# Master-Slave.net
KiCad netlist of a schematic drawn in Altium Designer
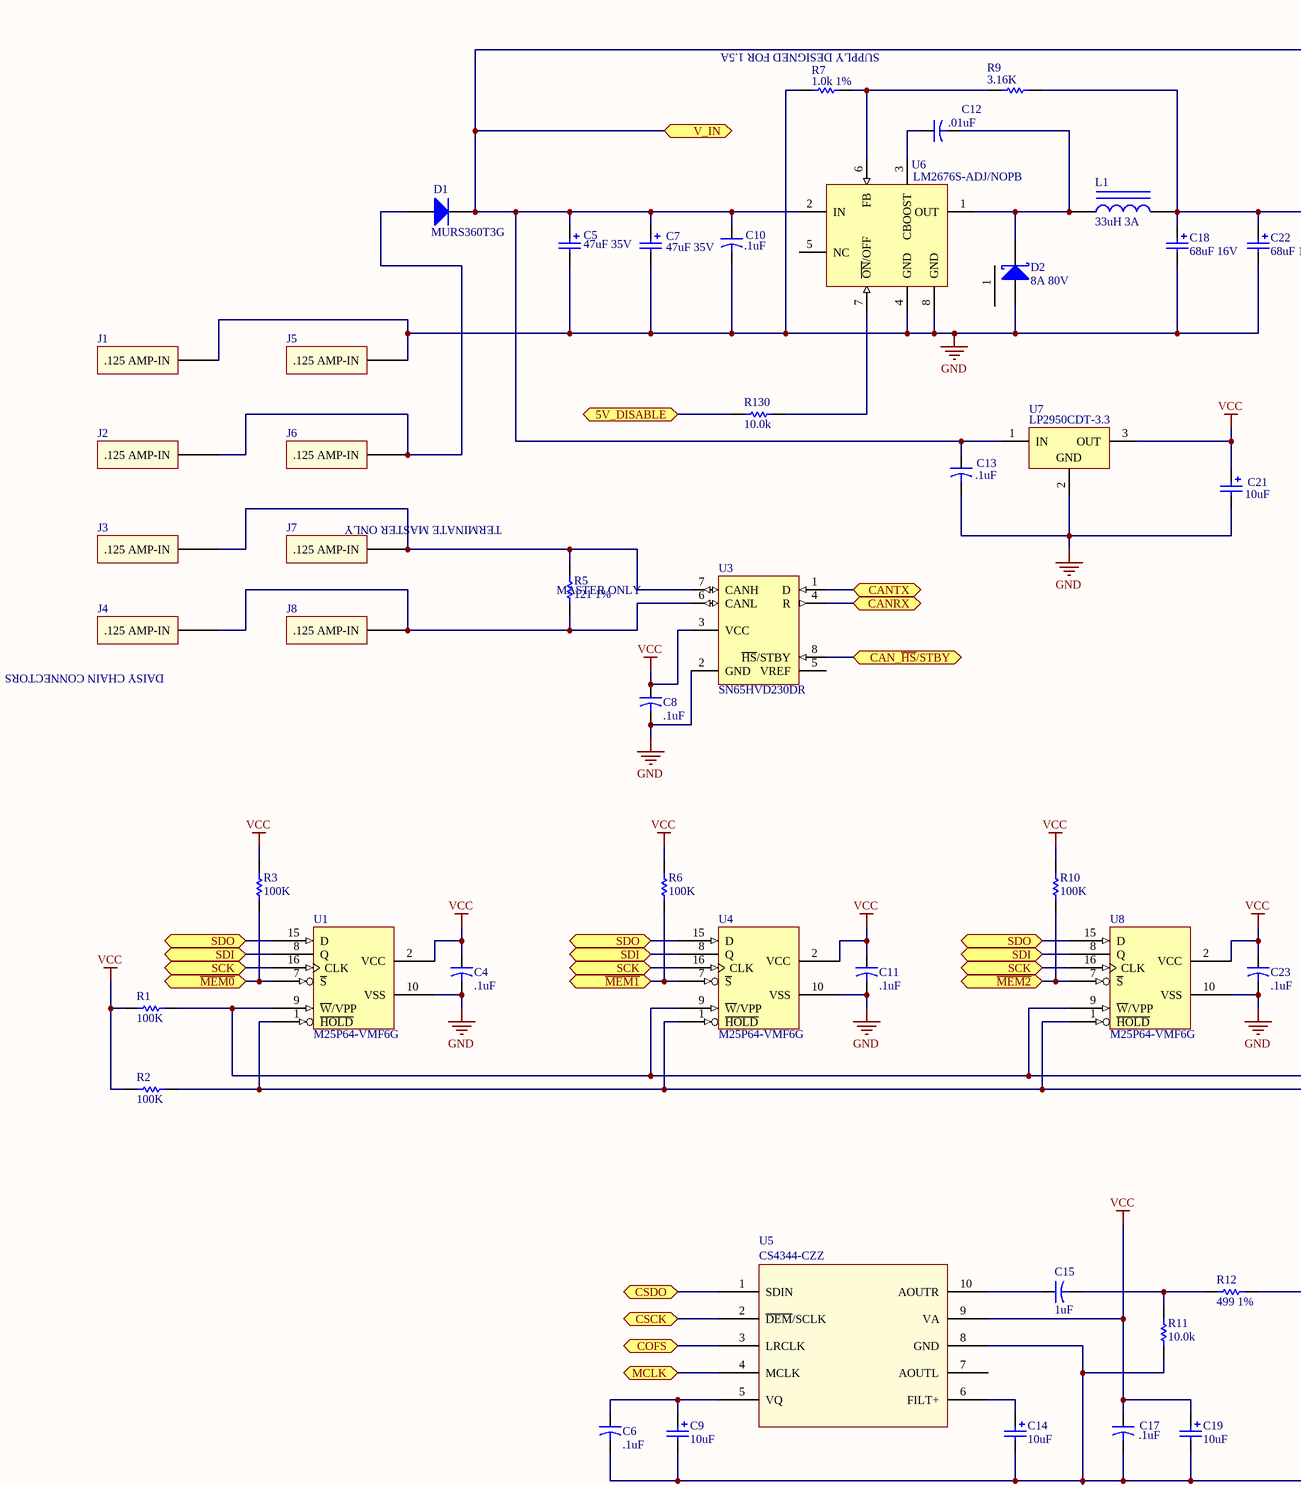
[diagram p0: Master-Slave.SchDoc, top left]
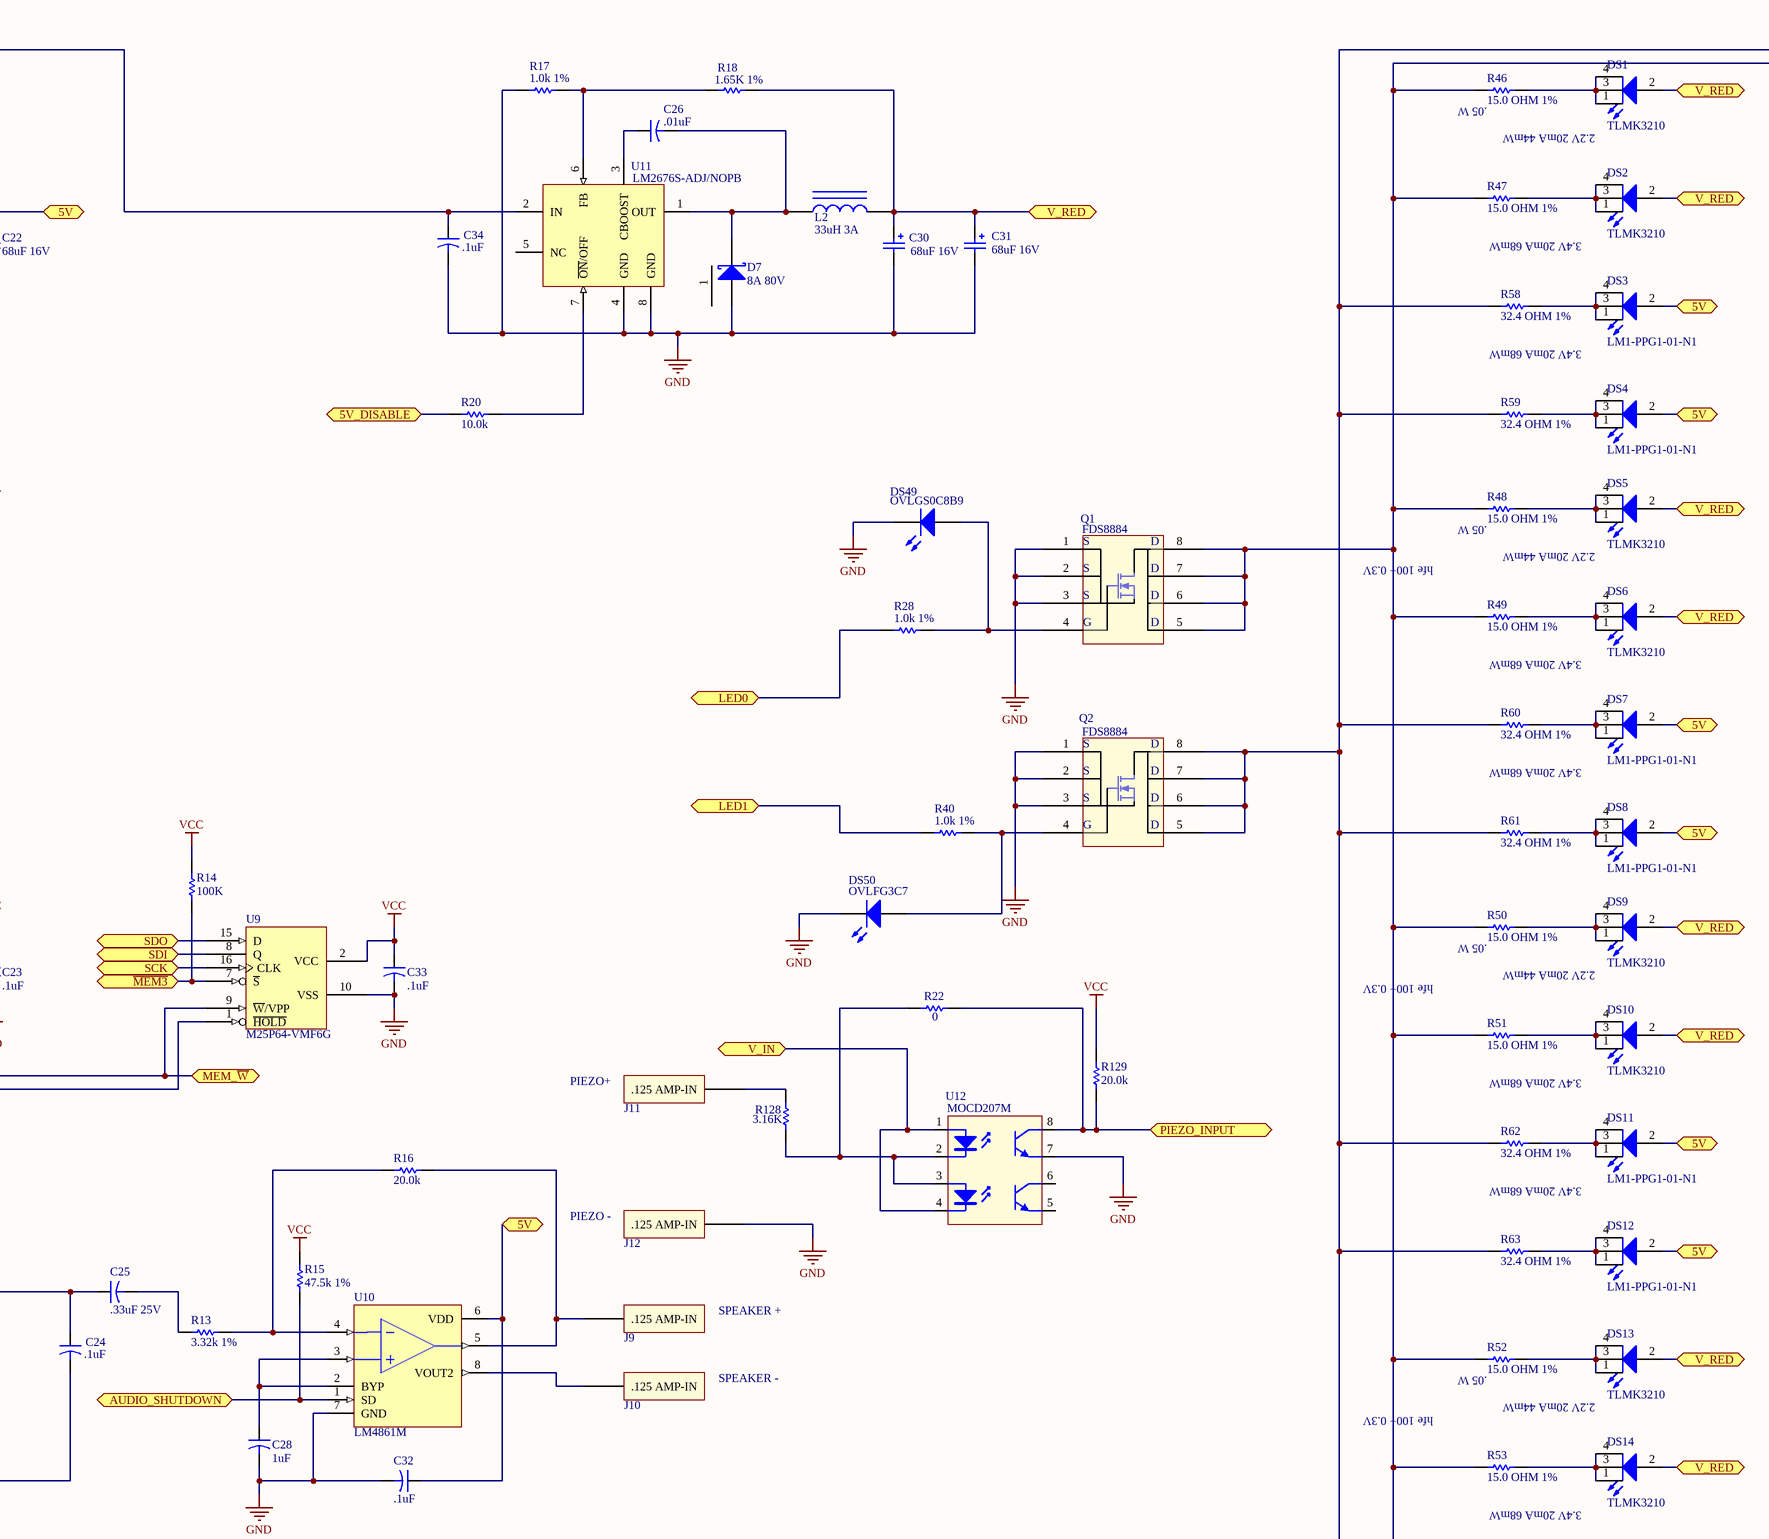
[diagram p1: Master-Slave.SchDoc, top middle]
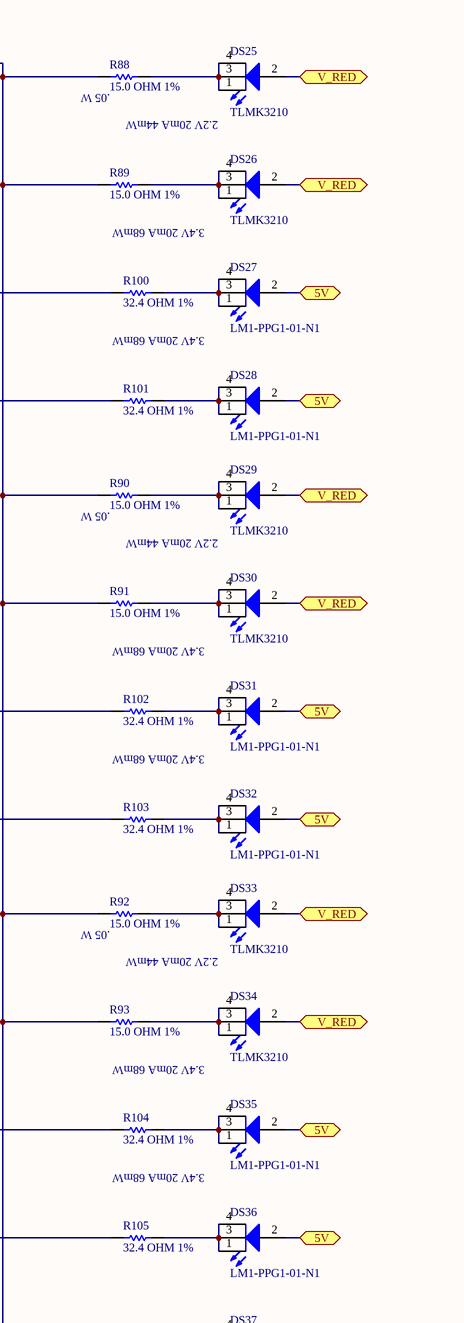
[diagram p2: Master-Slave.SchDoc, top right]
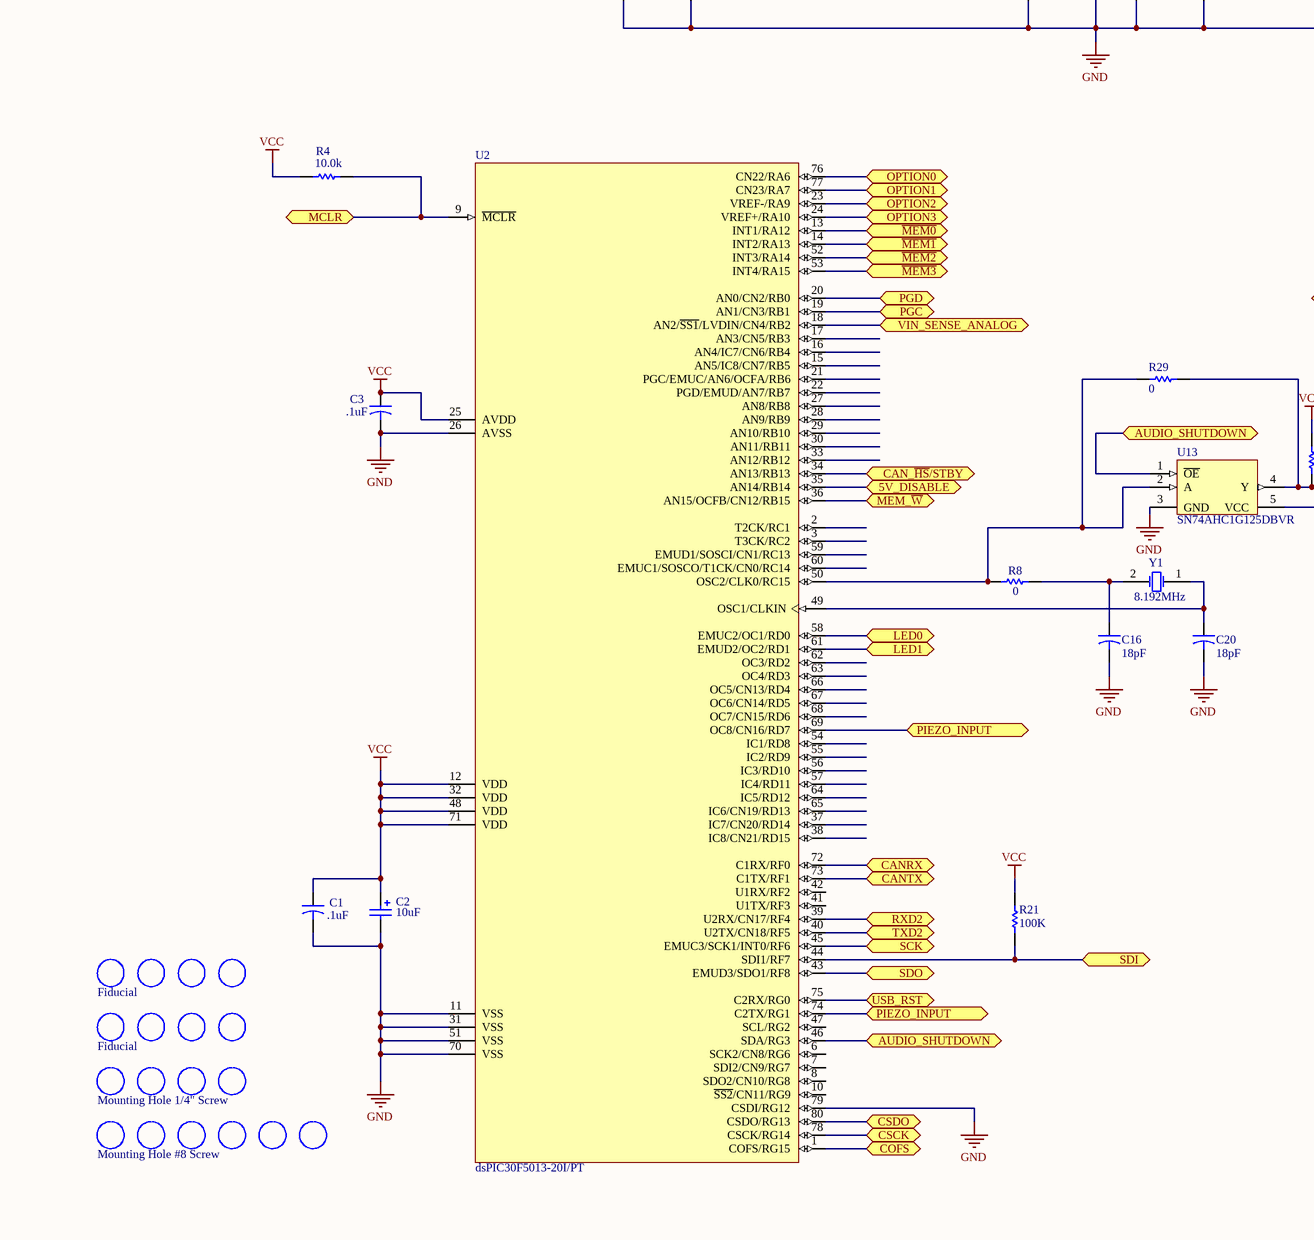
[diagram p3: Master-Slave.SchDoc, bottom left]
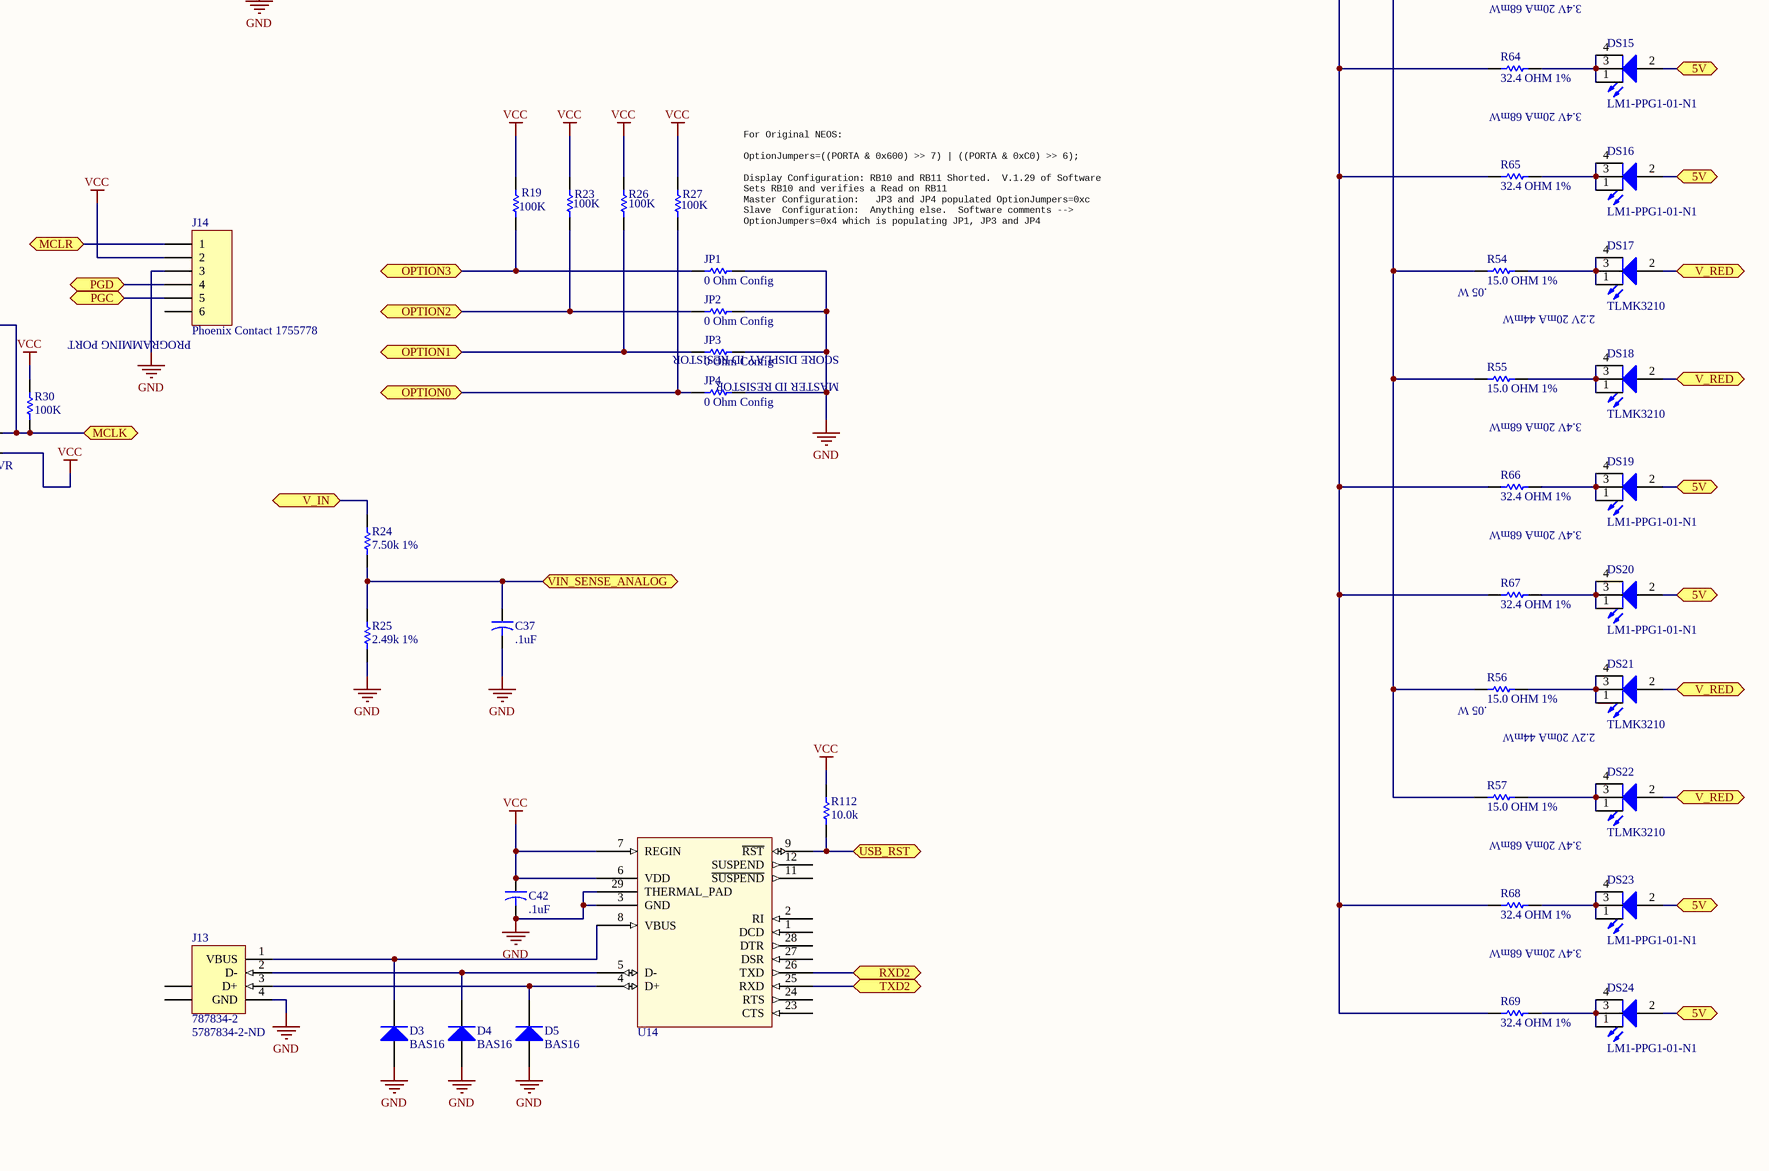
[diagram p4: Master-Slave.SchDoc, bottom middle]
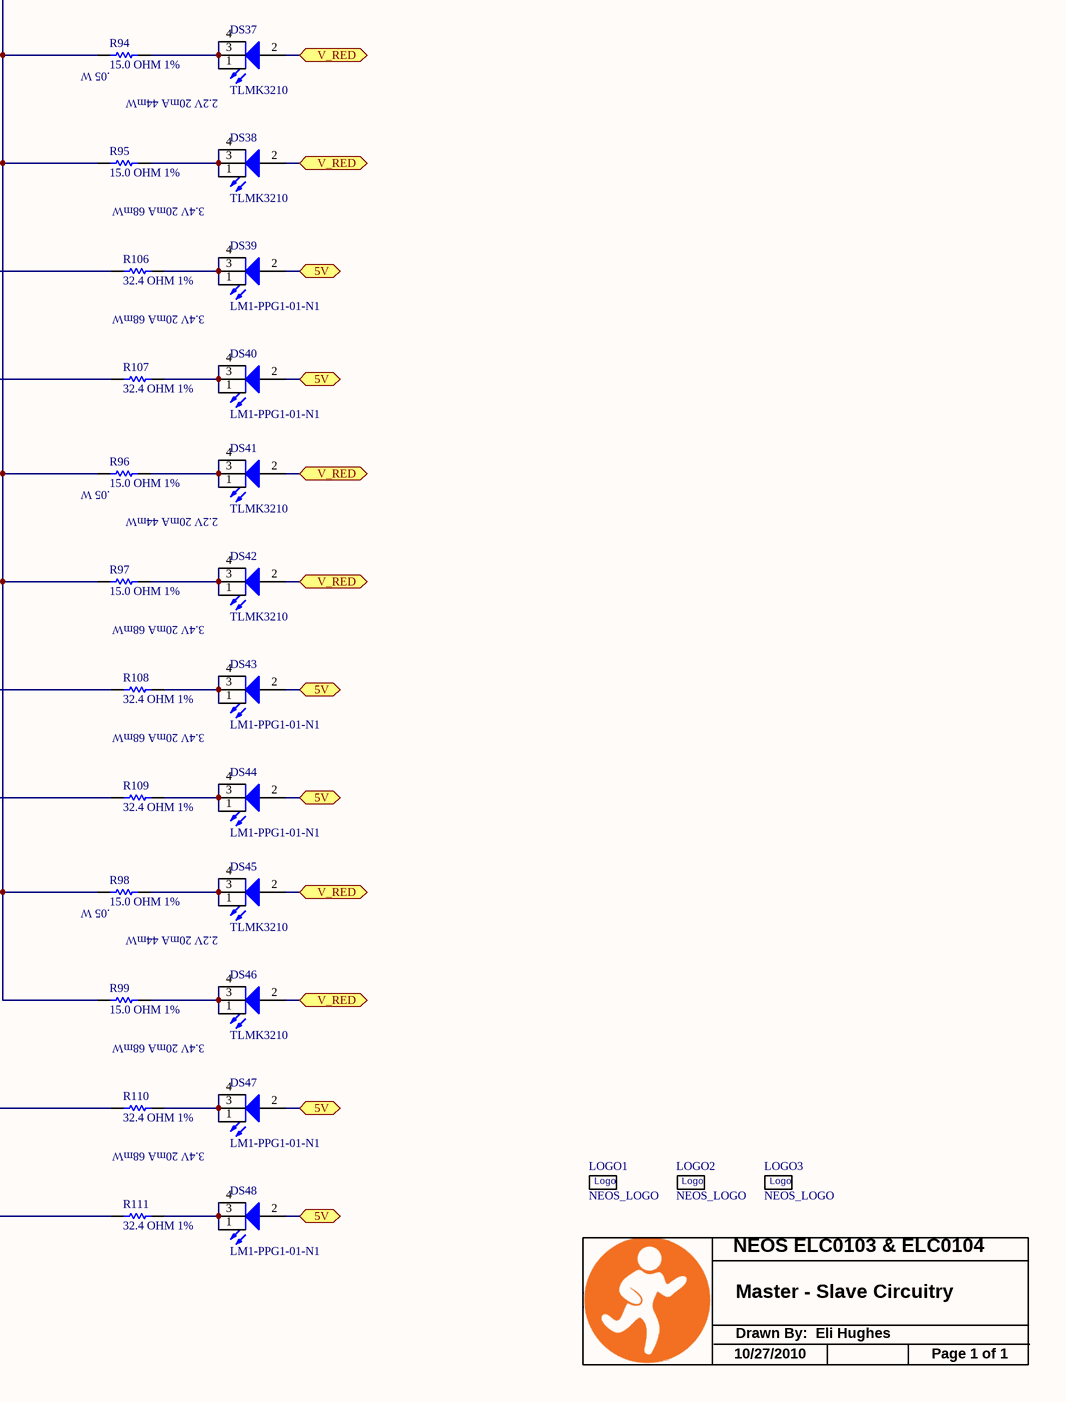
[diagram p5: Master-Slave.SchDoc, bottom right]

(export (version "E")
  (design (tool "Eeschema 10.0.6"))
  (components
    (comp (ref "C1")
      (value ".1uF")
      (footprint "C0805")
      (description "CAP .10UF 50V CERAMIC X7R 0805")
      (fields
        (field (name "MANUFACTURER") "Kemet")
        (field (name "MANUFACTURER PART NUMBER") "C0805C104K5RACTU")
      )
      (libsource (lib "") (part "C#S/C0805C104K5RACK_1"))
    )
    (comp (ref "C2")
      (value "10uF")
      (footprint "API:C4X5.8")
      (description "CAP ELECT 10UF 16V FK SMD")
      (fields
        (field (name "MANUFACTURER") "Panasonic - ECG")
        (field (name "MANUFACTURER PART NUMBER") "EEE-FK1C100R")
      )
      (libsource (lib "API") (part "C#S/EEEFK1C100RP"))
    )
    (comp (ref "C3")
      (value ".1uF")
      (footprint "C0805")
      (description "CAP .10UF 50V CERAMIC X7R 0805")
      (fields
        (field (name "MANUFACTURER") "Kemet")
        (field (name "MANUFACTURER PART NUMBER") "C0805C104K5RACTU")
      )
      (libsource (lib "") (part "C#S/C0805C104K5RACK_1"))
    )
    (comp (ref "C4")
      (value ".1uF")
      (footprint "C0805")
      (description "CAP .10UF 50V CERAMIC X7R 0805")
      (fields
        (field (name "MANUFACTURER") "Kemet")
        (field (name "MANUFACTURER PART NUMBER") "C0805C104K5RACTU")
      )
      (libsource (lib "API") (part "C#S/C0805C104K5RACK"))
    )
    (comp (ref "C5")
      (value "47uF 35V")
      (footprint "C EIA7343-43 (X)")
      (description "CAPACITOR TANT 47UF 35V 10% SMD 7343-43 (EIA)")
      (fields
        (field (name "MANUFACTURER") "Kemet")
        (field (name "MANUFACTURER PART NUMBER") "T491X476K035AT")
      )
      (libsource (lib "API") (part "C#S/T491X476K035ATK"))
    )
    (comp (ref "C6")
      (value ".1uF")
      (footprint "C0805")
      (description "CAP .10UF 50V CERAMIC X7R 0805")
      (fields
        (field (name "MANUFACTURER") "Kemet")
        (field (name "MANUFACTURER PART NUMBER") "C0805C104K5RACTU")
      )
      (libsource (lib "API") (part "C#S/C0805C104K5RACK"))
    )
    (comp (ref "C7")
      (value "47uF 35V")
      (footprint "C EIA7343-43 (X)")
      (description "CAPACITOR TANT 47UF 35V 10% SMD 7343-43 (EIA)")
      (fields
        (field (name "MANUFACTURER") "Kemet")
        (field (name "MANUFACTURER PART NUMBER") "T491X476K035AT")
      )
      (libsource (lib "API") (part "C#S/T491X476K035ATK"))
    )
    (comp (ref "C8")
      (value ".1uF")
      (footprint "C0805")
      (description "CAP .10UF 50V CERAMIC X7R 0805")
      (fields
        (field (name "MANUFACTURER") "Kemet")
        (field (name "MANUFACTURER PART NUMBER") "C0805C104K5RACTU")
      )
      (libsource (lib "API") (part "C#S/C0805C104K5RACK"))
    )
    (comp (ref "C9")
      (value "10uF")
      (footprint "API:C4X5.8")
      (description "CAP ELECT 10UF 16V FK SMD")
      (fields
        (field (name "MANUFACTURER") "Panasonic - ECG")
        (field (name "MANUFACTURER PART NUMBER") "EEE-FK1C100R")
      )
      (libsource (lib "API") (part "C#S/EEEFK1C100RP"))
    )
    (comp (ref "C10")
      (value ".1uF")
      (footprint "C0805")
      (description "CAP .10UF 50V CERAMIC X7R 0805")
      (fields
        (field (name "MANUFACTURER") "Kemet")
        (field (name "MANUFACTURER PART NUMBER") "C0805C104K5RACTU")
      )
      (libsource (lib "API") (part "C#S/C0805C104K5RACK"))
    )
    (comp (ref "C11")
      (value ".1uF")
      (footprint "C0805")
      (description "CAP .10UF 50V CERAMIC X7R 0805")
      (fields
        (field (name "MANUFACTURER") "Kemet")
        (field (name "MANUFACTURER PART NUMBER") "C0805C104K5RACTU")
      )
      (libsource (lib "API") (part "C#S/C0805C104K5RACK"))
    )
    (comp (ref "C12")
      (value ".01uF")
      (footprint "API:C0805")
      (description "CAP 10000PF 50V CERAMIC X7R 0805")
      (fields
        (field (name "MANUFACTURER") "Kemet")
        (field (name "MANUFACTURER PART NUMBER") "C0805C103K5RACTU")
      )
      (libsource (lib "API") (part "C#S/C0805C103K5RAC"))
    )
    (comp (ref "C13")
      (value ".1uF")
      (footprint "C0805")
      (description "CAP .10UF 50V CERAMIC X7R 0805")
      (fields
        (field (name "MANUFACTURER") "Kemet")
        (field (name "MANUFACTURER PART NUMBER") "C0805C104K5RACTU")
      )
      (libsource (lib "API") (part "C#S/C0805C104K5RACK"))
    )
    (comp (ref "C14")
      (value "10uF")
      (footprint "C4X5.8")
      (description "CAP ELECT 10UF 16V FK SMD")
      (fields
        (field (name "MANUFACTURER") "Panasonic - ECG")
        (field (name "MANUFACTURER PART NUMBER") "EEE-FK1C100R")
      )
      (libsource (lib "API") (part "C#S/EEEFK1C100RP"))
    )
    (comp (ref "C15")
      (value "1uF")
      (footprint "API:R1206")
      (description "CAP 1UF 25V CERAMIC X7R 1206")
      (fields
        (field (name "MANUFACTURER") "Panasonic - ECG")
        (field (name "MANUFACTURER PART NUMBER") "ECJ-3YB1E105K")
      )
      (libsource (lib "API") (part "C#S/ECJ3YB1E105KP"))
    )
    (comp (ref "C16")
      (value "18pF")
      (footprint "API:C0805")
      (description "CAP CERAMIC 18PF 50V NP0 0805")
      (fields
        (field (name "MANUFACTURER") "Kemet")
        (field (name "MANUFACTURER PART NUMBER") "C0805C180J5GACTU")
      )
      (libsource (lib "API") (part "C#S/C0805C180J5GACTUK"))
    )
    (comp (ref "C17")
      (value ".1uF")
      (footprint "C0805")
      (description "CAP .10UF 50V CERAMIC X7R 0805")
      (fields
        (field (name "MANUFACTURER") "Kemet")
        (field (name "MANUFACTURER PART NUMBER") "C0805C104K5RACTU")
      )
      (libsource (lib "API") (part "C#S/C0805C104K5RACK"))
    )
    (comp (ref "C18")
      (value "68uF 16V")
      (footprint "API:C7343")
      (description "CAPACITOR TANT 68UF 16V 10% SMD")
      (fields
        (field (name "MANUFACTURER") "Kemet")
        (field (name "MANUFACTURER PART NUMBER") "T495D686K016ATE150")
      )
      (libsource (lib "API") (part "C#S/T495D686K016ATEK"))
    )
    (comp (ref "C19")
      (value "10uF")
      (footprint "API:C4X5.8")
      (description "CAP ELECT 10UF 16V FK SMD")
      (fields
        (field (name "MANUFACTURER") "Panasonic - ECG")
        (field (name "MANUFACTURER PART NUMBER") "EEE-FK1C100R")
      )
      (libsource (lib "API") (part "C#S/EEEFK1C100RP"))
    )
    (comp (ref "C20")
      (value "18pF")
      (footprint "API:C0805")
      (description "CAP CERAMIC 18PF 50V NP0 0805")
      (fields
        (field (name "MANUFACTURER") "Kemet")
        (field (name "MANUFACTURER PART NUMBER") "C0805C180J5GACTU")
      )
      (libsource (lib "API") (part "C#S/C0805C180J5GACTUK"))
    )
    (comp (ref "C21")
      (value "10uF")
      (footprint "API:C4X5.8")
      (description "CAP ELECT 10UF 16V FK SMD")
      (fields
        (field (name "MANUFACTURER") "Panasonic - ECG")
        (field (name "MANUFACTURER PART NUMBER") "EEE-FK1C100R")
      )
      (libsource (lib "API") (part "C#S/EEEFK1C100RP"))
    )
    (comp (ref "C22")
      (value "68uF 16V")
      (footprint "API:C7343")
      (description "CAPACITOR TANT 68UF 16V 10% SMD")
      (fields
        (field (name "MANUFACTURER") "Kemet")
        (field (name "MANUFACTURER PART NUMBER") "T495D686K016ATE150")
      )
      (libsource (lib "API") (part "C#S/T495D686K016ATEK"))
    )
    (comp (ref "C23")
      (value ".1uF")
      (footprint "C0805")
      (description "CAP .10UF 50V CERAMIC X7R 0805")
      (fields
        (field (name "MANUFACTURER") "Kemet")
        (field (name "MANUFACTURER PART NUMBER") "C0805C104K5RACTU")
      )
      (libsource (lib "API") (part "C#S/C0805C104K5RACK"))
    )
    (comp (ref "C24")
      (value ".1uF")
      (footprint "C0805")
      (description "CAP .10UF 50V CERAMIC X7R 0805")
      (fields
        (field (name "MANUFACTURER") "Kemet")
        (field (name "MANUFACTURER PART NUMBER") "C0805C104K5RACTU")
      )
      (libsource (lib "API") (part "C#S/C0805C104K5RACK"))
    )
    (comp (ref "C25")
      (value ".33uF 25V")
      (footprint "API:R1206")
      (description "CAP .33UF 25V CERAMIC X7R 1206")
      (fields
        (field (name "MANUFACTURER") "Panasonic - ECG")
        (field (name "MANUFACTURER PART NUMBER") "ECJ-3VB1E334K")
      )
      (libsource (lib "API") (part "C#S/ECJ3VB1E334KP"))
    )
    (comp (ref "C26")
      (value ".01uF")
      (footprint "API:C0805")
      (description "CAP 10000PF 50V CERAMIC X7R 0805")
      (fields
        (field (name "MANUFACTURER") "Kemet")
        (field (name "MANUFACTURER PART NUMBER") "C0805C103K5RACTU")
      )
      (libsource (lib "API") (part "C#S/C0805C103K5RAC"))
    )
    (comp (ref "C28")
      (value "1uF")
      (footprint "API:R1206")
      (description "CAP 1UF 25V CERAMIC X7R 1206")
      (fields
        (field (name "MANUFACTURER") "Panasonic - ECG")
        (field (name "MANUFACTURER PART NUMBER") "ECJ-3YB1E105K")
      )
      (libsource (lib "API") (part "C#S/ECJ3YB1E105KP"))
    )
    (comp (ref "C30")
      (value "68uF 16V")
      (footprint "C7343")
      (description "CAPACITOR TANT 68UF 16V 10% SMD")
      (fields
        (field (name "MANUFACTURER") "Kemet")
        (field (name "MANUFACTURER PART NUMBER") "T495D686K016ATE150")
      )
      (libsource (lib "API") (part "C#S/T495D686K016ATEK"))
    )
    (comp (ref "C31")
      (value "68uF 16V")
      (footprint "API:C7343")
      (description "CAPACITOR TANT 68UF 16V 10% SMD")
      (fields
        (field (name "MANUFACTURER") "Kemet")
        (field (name "MANUFACTURER PART NUMBER") "T495D686K016ATE150")
      )
      (libsource (lib "API") (part "C#S/T495D686K016ATEK"))
    )
    (comp (ref "C32")
      (value ".1uF")
      (footprint "C0805")
      (description "CAP .10UF 50V CERAMIC X7R 0805")
      (fields
        (field (name "MANUFACTURER") "Kemet")
        (field (name "MANUFACTURER PART NUMBER") "C0805C104K5RACTU")
      )
      (libsource (lib "API") (part "C#S/C0805C104K5RACK"))
    )
    (comp (ref "C33")
      (value ".1uF")
      (footprint "C0805")
      (description "CAP .10UF 50V CERAMIC X7R 0805")
      (fields
        (field (name "MANUFACTURER") "Kemet")
        (field (name "MANUFACTURER PART NUMBER") "C0805C104K5RACTU")
      )
      (libsource (lib "API") (part "C#S/C0805C104K5RACK"))
    )
    (comp (ref "C34")
      (value ".1uF")
      (footprint "C0805")
      (description "CAP .10UF 50V CERAMIC X7R 0805")
      (fields
        (field (name "MANUFACTURER") "Kemet")
        (field (name "MANUFACTURER PART NUMBER") "C0805C104K5RACTU")
      )
      (libsource (lib "API") (part "C#S/C0805C104K5RACK"))
    )
    (comp (ref "C37")
      (value ".1uF")
      (footprint "C0805")
      (description "CAP .10UF 50V CERAMIC X7R 0805")
      (fields
        (field (name "MANUFACTURER") "Kemet")
        (field (name "MANUFACTURER PART NUMBER") "C0805C104K5RACTU")
      )
      (libsource (lib "API") (part "C#S/C0805C104K5RACK"))
    )
    (comp (ref "C42")
      (value ".1uF")
      (footprint "C0805")
      (description "CAP .10UF 50V CERAMIC X7R 0805")
      (fields
        (field (name "MANUFACTURER") "Kemet")
        (field (name "MANUFACTURER PART NUMBER") "C0805C104K5RACTU")
      )
      (libsource (lib "API") (part "C#S/C0805C104K5RACK"))
    )
    (comp (ref "D1")
      (value "DIODE ULTRA FAST 3A 600V SMC")
      (footprint "API:DIODE_SMC")
      (fields
        (field (name "MANUFACTURER") "ON Semiconductor")
        (field (name "MANUFACTURER PART NUMBER") "MURS360T3G")
      )
      (libsource (lib "API") (part "D#S/MURS360T3GM"))
    )
    (comp (ref "D2")
      (value "8A 80V")
      (footprint "API:D2PAK")
      (description "DIODE SCHOTTKY 80V 8A D2PAK")
      (fields
        (field (name "MANUFACTURER") "Vishay IR")
        (field (name "MANUFACTURER PART NUMBER") "8TQ100SPBF")
      )
      (libsource (lib "API") (part "D#S/8TQ080SPBFZ"))
    )
    (comp (ref "D3")
      (value "BAS16")
      (footprint "API:SOT23")
      (description "Diodes Inc BAS16 75V 200mA")
      (fields
        (field (name "MANUFACTURER") "Diodes Inc")
        (field (name "MANUFACTURER PART NUMBER") "BAS16-7-F")
      )
      (libsource (lib "API") (part "D#S/BAS167F0D"))
    )
    (comp (ref "D4")
      (value "BAS16")
      (footprint "API:SOT23")
      (description "Diodes Inc BAS16 75V 200mA")
      (fields
        (field (name "MANUFACTURER") "Diodes Inc")
        (field (name "MANUFACTURER PART NUMBER") "BAS16-7-F")
      )
      (libsource (lib "API") (part "D#S/BAS167F0D"))
    )
    (comp (ref "D5")
      (value "BAS16")
      (footprint "API:SOT23")
      (description "Diodes Inc BAS16 75V 200mA")
      (fields
        (field (name "MANUFACTURER") "Diodes Inc")
        (field (name "MANUFACTURER PART NUMBER") "BAS16-7-F")
      )
      (libsource (lib "API") (part "D#S/BAS167F0D"))
    )
    (comp (ref "D7")
      (value "8A 80V")
      (footprint "API:D2PAK")
      (description "DIODE SCHOTTKY 80V 8A D2PAK")
      (fields
        (field (name "MANUFACTURER") "Vishay IR")
        (field (name "MANUFACTURER PART NUMBER") "8TQ100SPBF")
      )
      (libsource (lib "API") (part "D#S/8TQ080SPBFZ"))
    )
    (comp (ref "DS1")
      (value "TLMK3210")
      (footprint "API:L#S/TLMK3210Z")
      (description "Vishay Red LED PLCC-3")
      (fields
        (field (name "MANUFACTURER") "Vishay")
        (field (name "MANUFACTURER PART NUMBER") "TLMK3210-GS08")
      )
      (libsource (lib "API") (part "L#S/TLMK3210"))
    )
    (comp (ref "DS2")
      (value "TLMK3210")
      (footprint "API:L#S/TLMK3210Z")
      (description "Vishay Red LED PLCC-3")
      (fields
        (field (name "MANUFACTURER") "Vishay")
        (field (name "MANUFACTURER PART NUMBER") "TLMK3210-GS08")
      )
      (libsource (lib "API") (part "L#S/TLMK3210"))
    )
    (comp (ref "DS3")
      (value "LM1-PPG1-01-N1")
      (footprint "L#S/TLMK3210Z")
      (description "120-degree, 3.3 x 3.5-mm, SMT LED in green color with water-transparent lens")
      (fields (field (name "MANUFACTURER") "Cree"))
      (libsource (lib "API") (part "L#S/LM1PPG103N1Z"))
    )
    (comp (ref "DS4")
      (value "LM1-PPG1-01-N1")
      (footprint "L#S/TLMK3210Z")
      (description "120-degree, 3.3 x 3.5-mm, SMT LED in green color with water-transparent lens")
      (fields (field (name "MANUFACTURER") "Cree"))
      (libsource (lib "API") (part "L#S/LM1PPG103N1Z"))
    )
    (comp (ref "DS5")
      (value "TLMK3210")
      (footprint "API:L#S/TLMK3210Z")
      (description "Vishay Red LED PLCC-3")
      (fields
        (field (name "MANUFACTURER") "Vishay")
        (field (name "MANUFACTURER PART NUMBER") "TLMK3210-GS08")
      )
      (libsource (lib "API") (part "L#S/TLMK3210"))
    )
    (comp (ref "DS6")
      (value "TLMK3210")
      (footprint "API:L#S/TLMK3210Z")
      (description "Vishay Red LED PLCC-3")
      (fields
        (field (name "MANUFACTURER") "Vishay")
        (field (name "MANUFACTURER PART NUMBER") "TLMK3210-GS08")
      )
      (libsource (lib "API") (part "L#S/TLMK3210"))
    )
    (comp (ref "DS7")
      (value "LM1-PPG1-01-N1")
      (footprint "L#S/TLMK3210Z")
      (description "120-degree, 3.3 x 3.5-mm, SMT LED in green color with water-transparent lens")
      (fields (field (name "MANUFACTURER") "Cree"))
      (libsource (lib "API") (part "L#S/LM1PPG103N1Z"))
    )
    (comp (ref "DS8")
      (value "LM1-PPG1-01-N1")
      (footprint "L#S/TLMK3210Z")
      (description "120-degree, 3.3 x 3.5-mm, SMT LED in green color with water-transparent lens")
      (fields (field (name "MANUFACTURER") "Cree"))
      (libsource (lib "API") (part "L#S/LM1PPG103N1Z"))
    )
    (comp (ref "DS9")
      (value "TLMK3210")
      (footprint "API:L#S/TLMK3210Z")
      (description "Vishay Red LED PLCC-3")
      (fields
        (field (name "MANUFACTURER") "Vishay")
        (field (name "MANUFACTURER PART NUMBER") "TLMK3210-GS08")
      )
      (libsource (lib "API") (part "L#S/TLMK3210"))
    )
    (comp (ref "DS10")
      (value "TLMK3210")
      (footprint "API:L#S/TLMK3210Z")
      (description "Vishay Red LED PLCC-3")
      (fields
        (field (name "MANUFACTURER") "Vishay")
        (field (name "MANUFACTURER PART NUMBER") "TLMK3210-GS08")
      )
      (libsource (lib "API") (part "L#S/TLMK3210"))
    )
    (comp (ref "DS11")
      (value "LM1-PPG1-01-N1")
      (footprint "L#S/TLMK3210Z")
      (description "120-degree, 3.3 x 3.5-mm, SMT LED in green color with water-transparent lens")
      (fields (field (name "MANUFACTURER") "Cree"))
      (libsource (lib "API") (part "L#S/LM1PPG103N1Z"))
    )
    (comp (ref "DS12")
      (value "LM1-PPG1-01-N1")
      (footprint "L#S/TLMK3210Z")
      (description "120-degree, 3.3 x 3.5-mm, SMT LED in green color with water-transparent lens")
      (fields (field (name "MANUFACTURER") "Cree"))
      (libsource (lib "API") (part "L#S/LM1PPG103N1Z"))
    )
    (comp (ref "DS13")
      (value "TLMK3210")
      (footprint "API:L#S/TLMK3210Z")
      (description "Vishay Red LED PLCC-3")
      (fields
        (field (name "MANUFACTURER") "Vishay")
        (field (name "MANUFACTURER PART NUMBER") "TLMK3210-GS08")
      )
      (libsource (lib "API") (part "L#S/TLMK3210"))
    )
    (comp (ref "DS14")
      (value "TLMK3210")
      (footprint "API:L#S/TLMK3210Z")
      (description "Vishay Red LED PLCC-3")
      (fields
        (field (name "MANUFACTURER") "Vishay")
        (field (name "MANUFACTURER PART NUMBER") "TLMK3210-GS08")
      )
      (libsource (lib "API") (part "L#S/TLMK3210"))
    )
    (comp (ref "DS15")
      (value "LM1-PPG1-01-N1")
      (footprint "L#S/TLMK3210Z")
      (description "120-degree, 3.3 x 3.5-mm, SMT LED in green color with water-transparent lens")
      (fields (field (name "MANUFACTURER") "Cree"))
      (libsource (lib "API") (part "L#S/LM1PPG103N1Z"))
    )
    (comp (ref "DS16")
      (value "LM1-PPG1-01-N1")
      (footprint "L#S/TLMK3210Z")
      (description "120-degree, 3.3 x 3.5-mm, SMT LED in green color with water-transparent lens")
      (fields (field (name "MANUFACTURER") "Cree"))
      (libsource (lib "API") (part "L#S/LM1PPG103N1Z"))
    )
    (comp (ref "DS17")
      (value "TLMK3210")
      (footprint "API:L#S/TLMK3210Z")
      (description "Vishay Red LED PLCC-3")
      (fields
        (field (name "MANUFACTURER") "Vishay")
        (field (name "MANUFACTURER PART NUMBER") "TLMK3210-GS08")
      )
      (libsource (lib "API") (part "L#S/TLMK3210"))
    )
    (comp (ref "DS18")
      (value "TLMK3210")
      (footprint "API:L#S/TLMK3210Z")
      (description "Vishay Red LED PLCC-3")
      (fields
        (field (name "MANUFACTURER") "Vishay")
        (field (name "MANUFACTURER PART NUMBER") "TLMK3210-GS08")
      )
      (libsource (lib "API") (part "L#S/TLMK3210"))
    )
    (comp (ref "DS19")
      (value "LM1-PPG1-01-N1")
      (footprint "L#S/TLMK3210Z")
      (description "120-degree, 3.3 x 3.5-mm, SMT LED in green color with water-transparent lens")
      (fields (field (name "MANUFACTURER") "Cree"))
      (libsource (lib "API") (part "L#S/LM1PPG103N1Z"))
    )
    (comp (ref "DS20")
      (value "LM1-PPG1-01-N1")
      (footprint "L#S/TLMK3210Z")
      (description "120-degree, 3.3 x 3.5-mm, SMT LED in green color with water-transparent lens")
      (fields (field (name "MANUFACTURER") "Cree"))
      (libsource (lib "API") (part "L#S/LM1PPG103N1Z"))
    )
    (comp (ref "DS21")
      (value "TLMK3210")
      (footprint "API:L#S/TLMK3210Z")
      (description "Vishay Red LED PLCC-3")
      (fields
        (field (name "MANUFACTURER") "Vishay")
        (field (name "MANUFACTURER PART NUMBER") "TLMK3210-GS08")
      )
      (libsource (lib "API") (part "L#S/TLMK3210"))
    )
    (comp (ref "DS22")
      (value "TLMK3210")
      (footprint "API:L#S/TLMK3210Z")
      (description "Vishay Red LED PLCC-3")
      (fields
        (field (name "MANUFACTURER") "Vishay")
        (field (name "MANUFACTURER PART NUMBER") "TLMK3210-GS08")
      )
      (libsource (lib "API") (part "L#S/TLMK3210"))
    )
    (comp (ref "DS23")
      (value "LM1-PPG1-01-N1")
      (footprint "L#S/TLMK3210Z")
      (description "120-degree, 3.3 x 3.5-mm, SMT LED in green color with water-transparent lens")
      (fields (field (name "MANUFACTURER") "Cree"))
      (libsource (lib "API") (part "L#S/LM1PPG103N1Z"))
    )
    (comp (ref "DS24")
      (value "LM1-PPG1-01-N1")
      (footprint "L#S/TLMK3210Z")
      (description "120-degree, 3.3 x 3.5-mm, SMT LED in green color with water-transparent lens")
      (fields (field (name "MANUFACTURER") "Cree"))
      (libsource (lib "API") (part "L#S/LM1PPG103N1Z"))
    )
    (comp (ref "DS25")
      (value "TLMK3210")
      (footprint "API:L#S/TLMK3210Z")
      (description "Vishay Red LED PLCC-3")
      (fields
        (field (name "MANUFACTURER") "Vishay")
        (field (name "MANUFACTURER PART NUMBER") "TLMK3210-GS08")
      )
      (libsource (lib "API") (part "L#S/TLMK3210"))
    )
    (comp (ref "DS26")
      (value "TLMK3210")
      (footprint "API:L#S/TLMK3210Z")
      (description "Vishay Red LED PLCC-3")
      (fields
        (field (name "MANUFACTURER") "Vishay")
        (field (name "MANUFACTURER PART NUMBER") "TLMK3210-GS08")
      )
      (libsource (lib "API") (part "L#S/TLMK3210"))
    )
    (comp (ref "DS27")
      (value "LM1-PPG1-01-N1")
      (footprint "L#S/TLMK3210Z")
      (description "120-degree, 3.3 x 3.5-mm, SMT LED in green color with water-transparent lens")
      (fields (field (name "MANUFACTURER") "Cree"))
      (libsource (lib "API") (part "L#S/LM1PPG103N1Z"))
    )
    (comp (ref "DS28")
      (value "LM1-PPG1-01-N1")
      (footprint "L#S/TLMK3210Z")
      (description "120-degree, 3.3 x 3.5-mm, SMT LED in green color with water-transparent lens")
      (fields (field (name "MANUFACTURER") "Cree"))
      (libsource (lib "API") (part "L#S/LM1PPG103N1Z"))
    )
    (comp (ref "DS29")
      (value "TLMK3210")
      (footprint "API:L#S/TLMK3210Z")
      (description "Vishay Red LED PLCC-3")
      (fields
        (field (name "MANUFACTURER") "Vishay")
        (field (name "MANUFACTURER PART NUMBER") "TLMK3210-GS08")
      )
      (libsource (lib "API") (part "L#S/TLMK3210"))
    )
    (comp (ref "DS30")
      (value "TLMK3210")
      (footprint "API:L#S/TLMK3210Z")
      (description "Vishay Red LED PLCC-3")
      (fields
        (field (name "MANUFACTURER") "Vishay")
        (field (name "MANUFACTURER PART NUMBER") "TLMK3210-GS08")
      )
      (libsource (lib "API") (part "L#S/TLMK3210"))
    )
    (comp (ref "DS31")
      (value "LM1-PPG1-01-N1")
      (footprint "L#S/TLMK3210Z")
      (description "120-degree, 3.3 x 3.5-mm, SMT LED in green color with water-transparent lens")
      (fields (field (name "MANUFACTURER") "Cree"))
      (libsource (lib "API") (part "L#S/LM1PPG103N1Z"))
    )
    (comp (ref "DS32")
      (value "LM1-PPG1-01-N1")
      (footprint "L#S/TLMK3210Z")
      (description "120-degree, 3.3 x 3.5-mm, SMT LED in green color with water-transparent lens")
      (fields (field (name "MANUFACTURER") "Cree"))
      (libsource (lib "API") (part "L#S/LM1PPG103N1Z"))
    )
    (comp (ref "DS33")
      (value "TLMK3210")
      (footprint "API:L#S/TLMK3210Z")
      (description "Vishay Red LED PLCC-3")
      (fields
        (field (name "MANUFACTURER") "Vishay")
        (field (name "MANUFACTURER PART NUMBER") "TLMK3210-GS08")
      )
      (libsource (lib "API") (part "L#S/TLMK3210"))
    )
    (comp (ref "DS34")
      (value "TLMK3210")
      (footprint "API:L#S/TLMK3210Z")
      (description "Vishay Red LED PLCC-3")
      (fields
        (field (name "MANUFACTURER") "Vishay")
        (field (name "MANUFACTURER PART NUMBER") "TLMK3210-GS08")
      )
      (libsource (lib "API") (part "L#S/TLMK3210"))
    )
    (comp (ref "DS35")
      (value "LM1-PPG1-01-N1")
      (footprint "L#S/TLMK3210Z")
      (description "120-degree, 3.3 x 3.5-mm, SMT LED in green color with water-transparent lens")
      (fields (field (name "MANUFACTURER") "Cree"))
      (libsource (lib "API") (part "L#S/LM1PPG103N1Z"))
    )
    (comp (ref "DS36")
      (value "LM1-PPG1-01-N1")
      (footprint "L#S/TLMK3210Z")
      (description "120-degree, 3.3 x 3.5-mm, SMT LED in green color with water-transparent lens")
      (fields (field (name "MANUFACTURER") "Cree"))
      (libsource (lib "API") (part "L#S/LM1PPG103N1Z"))
    )
    (comp (ref "DS37")
      (value "TLMK3210")
      (footprint "API:L#S/TLMK3210Z")
      (description "Vishay Red LED PLCC-3")
      (fields
        (field (name "MANUFACTURER") "Vishay")
        (field (name "MANUFACTURER PART NUMBER") "TLMK3210-GS08")
      )
      (libsource (lib "API") (part "L#S/TLMK3210"))
    )
    (comp (ref "DS38")
      (value "TLMK3210")
      (footprint "API:L#S/TLMK3210Z")
      (description "Vishay Red LED PLCC-3")
      (fields
        (field (name "MANUFACTURER") "Vishay")
        (field (name "MANUFACTURER PART NUMBER") "TLMK3210-GS08")
      )
      (libsource (lib "API") (part "L#S/TLMK3210"))
    )
    (comp (ref "DS39")
      (value "LM1-PPG1-01-N1")
      (footprint "L#S/TLMK3210Z")
      (description "120-degree, 3.3 x 3.5-mm, SMT LED in green color with water-transparent lens")
      (fields (field (name "MANUFACTURER") "Cree"))
      (libsource (lib "API") (part "L#S/LM1PPG103N1Z"))
    )
    (comp (ref "DS40")
      (value "LM1-PPG1-01-N1")
      (footprint "L#S/TLMK3210Z")
      (description "120-degree, 3.3 x 3.5-mm, SMT LED in green color with water-transparent lens")
      (fields (field (name "MANUFACTURER") "Cree"))
      (libsource (lib "API") (part "L#S/LM1PPG103N1Z"))
    )
    (comp (ref "DS41")
      (value "TLMK3210")
      (footprint "API:L#S/TLMK3210Z")
      (description "Vishay Red LED PLCC-3")
      (fields
        (field (name "MANUFACTURER") "Vishay")
        (field (name "MANUFACTURER PART NUMBER") "TLMK3210-GS08")
      )
      (libsource (lib "API") (part "L#S/TLMK3210"))
    )
    (comp (ref "DS42")
      (value "TLMK3210")
      (footprint "API:L#S/TLMK3210Z")
      (description "Vishay Red LED PLCC-3")
      (fields
        (field (name "MANUFACTURER") "Vishay")
        (field (name "MANUFACTURER PART NUMBER") "TLMK3210-GS08")
      )
      (libsource (lib "API") (part "L#S/TLMK3210"))
    )
    (comp (ref "DS43")
      (value "LM1-PPG1-01-N1")
      (footprint "L#S/TLMK3210Z")
      (description "120-degree, 3.3 x 3.5-mm, SMT LED in green color with water-transparent lens")
      (fields (field (name "MANUFACTURER") "Cree"))
      (libsource (lib "API") (part "L#S/LM1PPG103N1Z"))
    )
    (comp (ref "DS44")
      (value "LM1-PPG1-01-N1")
      (footprint "L#S/TLMK3210Z")
      (description "120-degree, 3.3 x 3.5-mm, SMT LED in green color with water-transparent lens")
      (fields (field (name "MANUFACTURER") "Cree"))
      (libsource (lib "API") (part "L#S/LM1PPG103N1Z"))
    )
    (comp (ref "DS45")
      (value "TLMK3210")
      (footprint "API:L#S/TLMK3210Z")
      (description "Vishay Red LED PLCC-3")
      (fields
        (field (name "MANUFACTURER") "Vishay")
        (field (name "MANUFACTURER PART NUMBER") "TLMK3210-GS08")
      )
      (libsource (lib "API") (part "L#S/TLMK3210"))
    )
    (comp (ref "DS46")
      (value "TLMK3210")
      (footprint "API:L#S/TLMK3210Z")
      (description "Vishay Red LED PLCC-3")
      (fields
        (field (name "MANUFACTURER") "Vishay")
        (field (name "MANUFACTURER PART NUMBER") "TLMK3210-GS08")
      )
      (libsource (lib "API") (part "L#S/TLMK3210"))
    )
    (comp (ref "DS47")
      (value "LM1-PPG1-01-N1")
      (footprint "L#S/TLMK3210Z")
      (description "120-degree, 3.3 x 3.5-mm, SMT LED in green color with water-transparent lens")
      (fields (field (name "MANUFACTURER") "Cree"))
      (libsource (lib "API") (part "L#S/LM1PPG103N1Z"))
    )
    (comp (ref "DS48")
      (value "LM1-PPG1-01-N1")
      (footprint "L#S/TLMK3210Z")
      (description "120-degree, 3.3 x 3.5-mm, SMT LED in green color with water-transparent lens")
      (fields (field (name "MANUFACTURER") "Cree"))
      (libsource (lib "API") (part "L#S/LM1PPG103N1Z"))
    )
    (comp (ref "DS49")
      (value "OVLGS0C8B9")
      (footprint "LED T1-3/4 Flush")
      (description "LED 631NM TAPERED RED 5MM")
      (fields (field (name "MANUFACTURER") "TT Electronics/Optek Technology"))
      (libsource (lib "API") (part "LRCOVLFR3C7Z"))
    )
    (comp (ref "DS50")
      (value "OVLFG3C7")
      (footprint "LED T1-3/4 Flush")
      (description "LED 525NM ROUND GREEN 5MM")
      (fields (field (name "MANUFACTURER") "TT Electronics/Optek Technology"))
      (libsource (lib "API") (part "LGCOVLFG3C7Z"))
    )
    (comp (ref "FID1")
      (value "Fiducial")
      (footprint "Fiducial")
      (fields
        (field (name "MANUFACTURER") "Manufacturer")
        (field (name "MANUFACTURER PART NUMBER") "Manufacturer Part Number")
      )
      (libsource (lib "API") (part "Fiducial"))
    )
    (comp (ref "FID2")
      (value "Fiducial")
      (footprint "Fiducial")
      (fields
        (field (name "MANUFACTURER") "Manufacturer")
        (field (name "MANUFACTURER PART NUMBER") "Manufacturer Part Number")
      )
      (libsource (lib "API") (part "Fiducial"))
    )
    (comp (ref "FID3")
      (value "Fiducial")
      (footprint "Fiducial")
      (fields
        (field (name "MANUFACTURER") "Manufacturer")
        (field (name "MANUFACTURER PART NUMBER") "Manufacturer Part Number")
      )
      (libsource (lib "API") (part "Fiducial"))
    )
    (comp (ref "FID4")
      (value "Fiducial")
      (footprint "Fiducial")
      (fields
        (field (name "MANUFACTURER") "Manufacturer")
        (field (name "MANUFACTURER PART NUMBER") "Manufacturer Part Number")
      )
      (libsource (lib "API") (part "Fiducial"))
    )
    (comp (ref "FID5")
      (value "Fiducial")
      (footprint "Fiducial")
      (fields
        (field (name "MANUFACTURER") "Manufacturer")
        (field (name "MANUFACTURER PART NUMBER") "Manufacturer Part Number")
      )
      (libsource (lib "API") (part "Fiducial"))
    )
    (comp (ref "FID6")
      (value "Fiducial")
      (footprint "Fiducial")
      (fields
        (field (name "MANUFACTURER") "Manufacturer")
        (field (name "MANUFACTURER PART NUMBER") "Manufacturer Part Number")
      )
      (libsource (lib "API") (part "Fiducial"))
    )
    (comp (ref "FID7")
      (value "Fiducial")
      (footprint "Fiducial")
      (fields
        (field (name "MANUFACTURER") "Manufacturer")
        (field (name "MANUFACTURER PART NUMBER") "Manufacturer Part Number")
      )
      (libsource (lib "API") (part "Fiducial"))
    )
    (comp (ref "FID8")
      (value "Fiducial")
      (footprint "Fiducial")
      (fields
        (field (name "MANUFACTURER") "Manufacturer")
        (field (name "MANUFACTURER PART NUMBER") "Manufacturer Part Number")
      )
      (libsource (lib "API") (part "Fiducial"))
    )
    (comp (ref "J1")
      (value "*")
      (footprint "API:WIRE_125")
      (fields
        (field (name "MANUFACTURER") "Manufacturer")
        (field (name "MANUFACTURER PART NUMBER") "Manufacturer Part Number")
      )
      (libsource (lib "API") (part "~125_WIRE"))
    )
    (comp (ref "J2")
      (value "*")
      (footprint "API:WIRE_125")
      (fields
        (field (name "MANUFACTURER") "Manufacturer")
        (field (name "MANUFACTURER PART NUMBER") "Manufacturer Part Number")
      )
      (libsource (lib "API") (part "~125_WIRE"))
    )
    (comp (ref "J3")
      (value "*")
      (footprint "API:WIRE_125")
      (fields
        (field (name "MANUFACTURER") "Manufacturer")
        (field (name "MANUFACTURER PART NUMBER") "Manufacturer Part Number")
      )
      (libsource (lib "API") (part "~125_WIRE"))
    )
    (comp (ref "J4")
      (value "*")
      (footprint "API:WIRE_125")
      (fields
        (field (name "MANUFACTURER") "Manufacturer")
        (field (name "MANUFACTURER PART NUMBER") "Manufacturer Part Number")
      )
      (libsource (lib "API") (part "~125_WIRE"))
    )
    (comp (ref "J5")
      (value "*")
      (footprint "API:WIRE_125")
      (fields
        (field (name "MANUFACTURER") "Manufacturer")
        (field (name "MANUFACTURER PART NUMBER") "Manufacturer Part Number")
      )
      (libsource (lib "API") (part "~125_WIRE"))
    )
    (comp (ref "J6")
      (value "*")
      (footprint "API:WIRE_125")
      (fields
        (field (name "MANUFACTURER") "Manufacturer")
        (field (name "MANUFACTURER PART NUMBER") "Manufacturer Part Number")
      )
      (libsource (lib "API") (part "~125_WIRE"))
    )
    (comp (ref "J7")
      (value "*")
      (footprint "API:WIRE_125")
      (fields
        (field (name "MANUFACTURER") "Manufacturer")
        (field (name "MANUFACTURER PART NUMBER") "Manufacturer Part Number")
      )
      (libsource (lib "API") (part "~125_WIRE"))
    )
    (comp (ref "J8")
      (value "*")
      (footprint "API:WIRE_125")
      (fields
        (field (name "MANUFACTURER") "Manufacturer")
        (field (name "MANUFACTURER PART NUMBER") "Manufacturer Part Number")
      )
      (libsource (lib "API") (part "~125_WIRE"))
    )
    (comp (ref "J9")
      (value "*")
      (footprint "API:WIRE_125")
      (fields
        (field (name "MANUFACTURER") "Manufacturer")
        (field (name "MANUFACTURER PART NUMBER") "Manufacturer Part Number")
      )
      (libsource (lib "") (part "~125_WIRE_1"))
    )
    (comp (ref "J10")
      (value "*")
      (footprint "API:WIRE_125")
      (fields
        (field (name "MANUFACTURER") "Manufacturer")
        (field (name "MANUFACTURER PART NUMBER") "Manufacturer Part Number")
      )
      (libsource (lib "") (part "~125_WIRE_1"))
    )
    (comp (ref "J11")
      (value "*")
      (footprint "API:WIRE_125")
      (fields
        (field (name "MANUFACTURER") "Manufacturer")
        (field (name "MANUFACTURER PART NUMBER") "Manufacturer Part Number")
      )
      (libsource (lib "API") (part "~125_WIRE"))
    )
    (comp (ref "J12")
      (value "*")
      (footprint "API:WIRE_125")
      (fields
        (field (name "MANUFACTURER") "Manufacturer")
        (field (name "MANUFACTURER PART NUMBER") "Manufacturer Part Number")
      )
      (libsource (lib "API") (part "~125_WIRE"))
    )
    (comp (ref "J13")
      (value "787834-2")
      (footprint "KUSBVX-BS1N")
      (description "USB 1.1, Vertical, Thru-Hole, B Type, Receptacle, 4 Position, Natural")
      (fields
        (field (name "MANUFACTURER") "Tyco Electronics")
        (field (name "MANUFACTURER PART NUMBER") "5787834-2")
        (field (name "SUPPLIER PART NUMBER 1") "5787834-2-ND")
        (field (name "PUBLISHER") "Altium Limited")
      )
      (libsource (lib "ScoreBoard") (part "787834-2"))
    )
    (comp (ref "J14")
      (value "Phoenix Contact 1755778")
      (footprint "JCPM5086VE0Z")
      (description "CONN HEADER VERT 6POS 5.08MM")
      (fields
        (field (name "MANUFACTURER") "Phoenix Contact")
        (field (name "MANUFACTURER PART NUMBER") "1755778")
      )
      (libsource (lib "API") (part "JCPM5086VE0Z"))
    )
    (comp (ref "JP1")
      (value "0 Ohm Config")
      (description "RES 0.0 OHM 1/8W 5% 0805 SMD")
      (fields
        (field (name "MANUFACTURER") "Panasonic - ECG")
        (field (name "MANUFACTURER PART NUMBER") "ERJ-6GEY0R00V")
      )
      (libsource (lib "API") (part "RS/ERJ6ENF"))
    )
    (comp (ref "JP2")
      (value "0 Ohm Config")
      (description "RES 0.0 OHM 1/8W 5% 0805 SMD")
      (fields
        (field (name "MANUFACTURER") "Panasonic - ECG")
        (field (name "MANUFACTURER PART NUMBER") "ERJ-6GEY0R00V")
      )
      (libsource (lib "API") (part "RS/ERJ6ENF"))
    )
    (comp (ref "JP3")
      (value "0 Ohm Config")
      (description "RES 0.0 OHM 1/8W 5% 0805 SMD")
      (fields
        (field (name "MANUFACTURER") "Panasonic - ECG")
        (field (name "MANUFACTURER PART NUMBER") "ERJ-6GEY0R00V")
      )
      (libsource (lib "API") (part "RS/ERJ6ENF"))
    )
    (comp (ref "JP4")
      (value "0 Ohm Config")
      (footprint "0805")
      (description "RES 0.0 OHM 1/8W 5% 0805 SMD")
      (fields
        (field (name "MANUFACTURER") "Panasonic - ECG")
        (field (name "MANUFACTURER PART NUMBER") "ERJ-6GEY0R00V")
      )
      (libsource (lib "API") (part "RS/ERJ6ENF"))
    )
    (comp (ref "L1")
      (value "33uH 3A")
      (footprint "API:IND/DO5022")
      (description "33uH 3A Surface Mount Inductor")
      (fields
        (field (name "MANUFACTURER") "CoilCraft")
        (field (name "MANUFACTURER PART NUMBER") "DO5022P-333MLB")
      )
      (libsource (lib "API") (part "N#S/DO5022P333Z"))
    )
    (comp (ref "L2")
      (value "33uH 3A")
      (footprint "API:IND/DO5022")
      (description "33uH 3A Surface Mount Inductor")
      (fields
        (field (name "MANUFACTURER") "CoilCraft")
        (field (name "MANUFACTURER PART NUMBER") "DO5022P-333MLB")
      )
      (libsource (lib "API") (part "N#S/DO5022P333Z"))
    )
    (comp (ref "LOGO1")
      (value "NEOS_LOGO")
      (footprint "NEOS_LOGO_0")
      (libsource (lib "eLogo") (part "NEOS_LOGO"))
    )
    (comp (ref "LOGO2")
      (value "NEOS_LOGO")
      (footprint "FULL_LOGO")
      (libsource (lib "eLogo") (part "NEOS_LOGO"))
    )
    (comp (ref "LOGO3")
      (value "NEOS_LOGO")
      (footprint "NEOS_LOGO_0")
      (libsource (lib "eLogo") (part "NEOS_LOGO"))
    )
    (comp (ref "M1")
      (value "Mounting Hole 1/4\" Screw")
      (footprint "MHole250")
      (fields
        (field (name "MANUFACTURER") "Manufacturer")
        (field (name "MANUFACTURER PART NUMBER") "Manufacturer Part Number")
      )
      (libsource (lib "Rays_Altium") (part "MountingHole_1/4"))
    )
    (comp (ref "M2")
      (value "Mounting Hole 1/4\" Screw")
      (footprint "MHole250")
      (fields
        (field (name "MANUFACTURER") "Manufacturer")
        (field (name "MANUFACTURER PART NUMBER") "Manufacturer Part Number")
      )
      (libsource (lib "Rays_Altium") (part "MountingHole_1/4"))
    )
    (comp (ref "M3")
      (value "Mounting Hole 1/4\" Screw")
      (footprint "MHole250")
      (fields
        (field (name "MANUFACTURER") "Manufacturer")
        (field (name "MANUFACTURER PART NUMBER") "Manufacturer Part Number")
      )
      (libsource (lib "Rays_Altium") (part "MountingHole_1/4"))
    )
    (comp (ref "M4")
      (value "Mounting Hole 1/4\" Screw")
      (footprint "MHole250")
      (fields
        (field (name "MANUFACTURER") "Manufacturer")
        (field (name "MANUFACTURER PART NUMBER") "Manufacturer Part Number")
      )
      (libsource (lib "Rays_Altium") (part "MountingHole_1/4"))
    )
    (comp (ref "M5")
      (value "Mounting Hole #8 Screw")
      (footprint "MHole#8")
      (fields
        (field (name "MANUFACTURER") "Manufacturer")
        (field (name "MANUFACTURER PART NUMBER") "Manufacturer Part Number")
      )
      (libsource (lib "Rays_Altium") (part "MountingHole_8"))
    )
    (comp (ref "M6")
      (value "Mounting Hole #8 Screw")
      (footprint "MHole#8")
      (fields
        (field (name "MANUFACTURER") "Manufacturer")
        (field (name "MANUFACTURER PART NUMBER") "Manufacturer Part Number")
      )
      (libsource (lib "Rays_Altium") (part "MountingHole_8"))
    )
    (comp (ref "M7")
      (value "Mounting Hole #8 Screw")
      (footprint "MHole#8")
      (fields
        (field (name "MANUFACTURER") "Manufacturer")
        (field (name "MANUFACTURER PART NUMBER") "Manufacturer Part Number")
      )
      (libsource (lib "Rays_Altium") (part "MountingHole_8"))
    )
    (comp (ref "M8")
      (value "Mounting Hole #8 Screw")
      (footprint "MHole#8")
      (fields
        (field (name "MANUFACTURER") "Manufacturer")
        (field (name "MANUFACTURER PART NUMBER") "Manufacturer Part Number")
      )
      (libsource (lib "Rays_Altium") (part "MountingHole_8"))
    )
    (comp (ref "M9")
      (value "Mounting Hole #8 Screw")
      (footprint "MHole#8")
      (fields
        (field (name "MANUFACTURER") "Manufacturer")
        (field (name "MANUFACTURER PART NUMBER") "Manufacturer Part Number")
      )
      (libsource (lib "Rays_Altium") (part "MountingHole_8"))
    )
    (comp (ref "M10")
      (value "Mounting Hole #8 Screw")
      (footprint "MHole#8")
      (fields
        (field (name "MANUFACTURER") "Manufacturer")
        (field (name "MANUFACTURER PART NUMBER") "Manufacturer Part Number")
      )
      (libsource (lib "Rays_Altium") (part "MountingHole_8"))
    )
    (comp (ref "Q1")
      (value "FDS8884")
      (footprint "SO8")
      (description "MOSFET N-CH 30V 8.5A 8-SOIC")
      (fields (field (name "MANUFACTURER") "Fairchild Semiconductor"))
      (libsource (lib "API") (part "Q#S/FDS8884F"))
    )
    (comp (ref "Q2")
      (value "FDS8884")
      (footprint "SO8")
      (description "MOSFET N-CH 30V 8.5A 8-SOIC")
      (fields (field (name "MANUFACTURER") "Fairchild Semiconductor"))
      (libsource (lib "API") (part "Q#S/FDS8884F"))
    )
    (comp (ref "R1")
      (value "100K")
      (footprint "R0805")
      (description "RES 100K OHM 1/8W 1% 0805 SMD")
      (fields
        (field (name "MANUFACTURER") "Panasonic - ECG")
        (field (name "MANUFACTURER PART NUMBER") "RC0805JR-07100KL")
      )
      (libsource (lib "API") (part "RS/ERJ6ENF"))
    )
    (comp (ref "R2")
      (value "100K")
      (footprint "R0805")
      (description "RES 100K OHM 1/8W 1% 0805 SMD")
      (fields
        (field (name "MANUFACTURER") "Panasonic - ECG")
        (field (name "MANUFACTURER PART NUMBER") "RC0805JR-07100KL")
      )
      (libsource (lib "API") (part "RS/ERJ6ENF"))
    )
    (comp (ref "R3")
      (value "100K")
      (footprint "R0805")
      (description "RES 100K OHM 1/8W 1% 0805 SMD")
      (fields
        (field (name "MANUFACTURER") "Panasonic - ECG")
        (field (name "MANUFACTURER PART NUMBER") "RC0805JR-07100KL")
      )
      (libsource (lib "API") (part "RS/ERJ6ENF"))
    )
    (comp (ref "R4")
      (value "10.0k")
      (footprint "R0805")
      (description "RES 10.0K OHM 1/8W 1% 0805 SMD")
      (fields
        (field (name "MANUFACTURER") "Panasonic - ECG")
        (field (name "MANUFACTURER PART NUMBER") "ERJ-6ENF1002V")
      )
      (libsource (lib "API") (part "RS/ERJ6ENF"))
    )
    (comp (ref "R5")
      (value "121 1%")
      (footprint "R1206")
      (description "RES 121 OHM 1/4W 1% 1206 SMD")
      (fields
        (field (name "MANUFACTURER") "Panasonic - ECG")
        (field (name "MANUFACTURER PART NUMBER") "ERJ-8ENF1210V")
      )
      (libsource (lib "API") (part "RS/ERJ8ENF"))
    )
    (comp (ref "R6")
      (value "100K")
      (footprint "R0805")
      (description "RES 100K OHM 1/8W 1% 0805 SMD")
      (fields
        (field (name "MANUFACTURER") "Panasonic - ECG")
        (field (name "MANUFACTURER PART NUMBER") "RC0805JR-07100KL")
      )
      (libsource (lib "API") (part "RS/ERJ6ENF"))
    )
    (comp (ref "R7")
      (value "1.0k 1%")
      (footprint "R0805")
      (description "RES 1.00K OHM 1/8W 1% 0805 SMD")
      (fields
        (field (name "MANUFACTURER") "Yageo")
        (field (name "MANUFACTURER PART NUMBER") "RC0805FR-071KL")
      )
      (libsource (lib "API") (part "RS/ERJ6ENF"))
    )
    (comp (ref "R8")
      (value "0")
      (footprint "R0805")
      (description "RES 0.0 OHM 1/8W 5% 0805 SMD")
      (fields
        (field (name "MANUFACTURER") "Panasonic - ECG")
        (field (name "MANUFACTURER PART NUMBER") "ERJ-6GEY0R00V")
      )
      (libsource (lib "API") (part "RS/ERJ6GEYJ"))
    )
    (comp (ref "R9")
      (value "3.16K")
      (footprint "R0805")
      (description "RES 3.16K OHM 1/8W 1% 0805 SMD")
      (fields
        (field (name "MANUFACTURER") "Panasonic - ECG")
        (field (name "MANUFACTURER PART NUMBER") "ERJ-6ENF3161V")
      )
      (libsource (lib "API") (part "RS/ERJ6ENF"))
    )
    (comp (ref "R10")
      (value "100K")
      (footprint "R0805")
      (description "RES 100K OHM 1/8W 1% 0805 SMD")
      (fields
        (field (name "MANUFACTURER") "Panasonic - ECG")
        (field (name "MANUFACTURER PART NUMBER") "RC0805JR-07100KL")
      )
      (libsource (lib "API") (part "RS/ERJ6ENF"))
    )
    (comp (ref "R11")
      (value "10.0k")
      (footprint "R0805")
      (description "RES 10.0K OHM 1/8W 1% 0805 SMD")
      (fields
        (field (name "MANUFACTURER") "Panasonic - ECG")
        (field (name "MANUFACTURER PART NUMBER") "ERJ-6ENF1002V")
      )
      (libsource (lib "API") (part "RS/ERJ6ENF"))
    )
    (comp (ref "R12")
      (value "499 1%")
      (footprint "R0805")
      (description "RES 499 OHM 1/8W 1% 0805 SMD")
      (fields
        (field (name "MANUFACTURER") "Panasonic - ECG")
        (field (name "MANUFACTURER PART NUMBER") "ERJ-6ENF4990V")
      )
      (libsource (lib "API") (part "RS/ERJ6ENF"))
    )
    (comp (ref "R13")
      (value "3.32k 1%")
      (footprint "R0805")
      (description "RES 3.32K OHM 1/8W 1% 0805 SMD")
      (fields
        (field (name "MANUFACTURER") "Panasonic - ECG")
        (field (name "MANUFACTURER PART NUMBER") "ERJ-6ENF3321V")
      )
      (libsource (lib "API") (part "RS/ERJ6ENF"))
    )
    (comp (ref "R14")
      (value "100K")
      (footprint "R0805")
      (description "RES 100K OHM 1/8W 1% 0805 SMD")
      (fields
        (field (name "MANUFACTURER") "Panasonic - ECG")
        (field (name "MANUFACTURER PART NUMBER") "RC0805JR-07100KL")
      )
      (libsource (lib "API") (part "RS/ERJ6ENF"))
    )
    (comp (ref "R15")
      (value "47.5k 1%")
      (footprint "R0805")
      (description "RES 47.5K OHM 1/8W 1% 0805 SMD")
      (fields
        (field (name "MANUFACTURER") "Panasonic - ECG")
        (field (name "MANUFACTURER PART NUMBER") "ERJ-6ENF4752V")
      )
      (libsource (lib "API") (part "RS/ERJ6ENF"))
    )
    (comp (ref "R16")
      (value "20.0k")
      (footprint "R0805")
      (description "RES 20.0K OHM 1/8W 1% 0805 SMD")
      (fields
        (field (name "MANUFACTURER") "Panasonic - ECG")
        (field (name "MANUFACTURER PART NUMBER") "ERJ-6ENF2002V")
      )
      (libsource (lib "API") (part "RS/ERJ6ENF"))
    )
    (comp (ref "R17")
      (value "1.0k 1%")
      (footprint "R0805")
      (description "RES 1.00K OHM 1/8W 1% 0805 SMD")
      (fields
        (field (name "MANUFACTURER") "Yageo")
        (field (name "MANUFACTURER PART NUMBER") "RC0805FR-071KL")
      )
      (libsource (lib "API") (part "RS/ERJ6ENF"))
    )
    (comp (ref "R18")
      (value "1.65K 1%")
      (footprint "R0805")
      (description "RES 1.65K OHM 1/8W 1% 0805 SMD")
      (fields
        (field (name "MANUFACTURER PART NUMBER") "ERJ-6ENF1651V")
        (field (name "MANUFACTURER") "Panasonic - ECG")
      )
      (libsource (lib "API") (part "RS/ERJ6ENF"))
    )
    (comp (ref "R19")
      (value "100K")
      (footprint "R0805")
      (description "RES 100K OHM 1/8W 1% 0805 SMD")
      (fields
        (field (name "MANUFACTURER") "Panasonic - ECG")
        (field (name "MANUFACTURER PART NUMBER") "RC0805JR-07100KL")
      )
      (libsource (lib "API") (part "RS/ERJ6ENF"))
    )
    (comp (ref "R20")
      (value "10.0k")
      (footprint "R0805")
      (description "RES 10.0K OHM 1/8W 1% 0805 SMD")
      (fields
        (field (name "MANUFACTURER") "Panasonic - ECG")
        (field (name "MANUFACTURER PART NUMBER") "ERJ-6ENF1002V")
      )
      (libsource (lib "API") (part "RS/ERJ6ENF"))
    )
    (comp (ref "R21")
      (value "100K")
      (footprint "R0805")
      (description "RES 100K OHM 1/8W 1% 0805 SMD")
      (fields
        (field (name "MANUFACTURER") "Panasonic - ECG")
        (field (name "MANUFACTURER PART NUMBER") "RC0805JR-07100KL")
      )
      (libsource (lib "API") (part "RS/ERJ6ENF"))
    )
    (comp (ref "R22")
      (value "0")
      (footprint "R0805")
      (description "RES 0.0 OHM 1/8W 5% 0805 SMD")
      (fields
        (field (name "MANUFACTURER") "Panasonic - ECG")
        (field (name "MANUFACTURER PART NUMBER") "ERJ-6GEY0R00V")
      )
      (libsource (lib "API") (part "RS/ERJ6GEYJ"))
    )
    (comp (ref "R23")
      (value "100K")
      (footprint "R0805")
      (description "RES 100K OHM 1/8W 1% 0805 SMD")
      (fields
        (field (name "MANUFACTURER") "Panasonic - ECG")
        (field (name "MANUFACTURER PART NUMBER") "RC0805JR-07100KL")
      )
      (libsource (lib "API") (part "RS/ERJ6ENF"))
    )
    (comp (ref "R24")
      (value "7.50k 1%")
      (footprint "R0805")
      (description "RES 7.50K OHM 1/8W 1% 0805 SMD")
      (fields
        (field (name "MANUFACTURER") "Panasonic - ECG")
        (field (name "MANUFACTURER PART NUMBER") "ERJ-6ENF7501V")
      )
      (libsource (lib "API") (part "RS/ERJ6ENF"))
    )
    (comp (ref "R25")
      (value "2.49k 1%")
      (description "RES 2.49K OHM 1/8W 1% 0805 SMD")
      (fields
        (field (name "MANUFACTURER") "Panasonic - ECG")
        (field (name "MANUFACTURER PART NUMBER") "ERJ-6ENF2491V")
      )
      (libsource (lib "API") (part "RS/ERJ6ENF"))
    )
    (comp (ref "R26")
      (value "100K")
      (footprint "R0805")
      (description "RES 100K OHM 1/8W 1% 0805 SMD")
      (fields
        (field (name "MANUFACTURER") "Panasonic - ECG")
        (field (name "MANUFACTURER PART NUMBER") "RC0805JR-07100KL")
      )
      (libsource (lib "API") (part "RS/ERJ6ENF"))
    )
    (comp (ref "R27")
      (value "100K")
      (footprint "R0805")
      (description "RES 100K OHM 1/8W 1% 0805 SMD")
      (fields
        (field (name "MANUFACTURER") "Panasonic - ECG")
        (field (name "MANUFACTURER PART NUMBER") "RC0805JR-07100KL")
      )
      (libsource (lib "API") (part "RS/ERJ6ENF"))
    )
    (comp (ref "R28")
      (value "1.0k 1%")
      (footprint "R0805")
      (description "RES 1.00K OHM 1/8W 1% 0805 SMD")
      (fields
        (field (name "MANUFACTURER") "Yageo")
        (field (name "MANUFACTURER PART NUMBER") "RC0805FR-071KL")
      )
      (libsource (lib "API") (part "RS/ERJ6ENF"))
    )
    (comp (ref "R29")
      (value "0")
      (footprint "R0805")
      (description "RES 0.0 OHM 1/8W 5% 0805 SMD")
      (fields
        (field (name "MANUFACTURER") "Panasonic - ECG")
        (field (name "MANUFACTURER PART NUMBER") "ERJ-6GEY0R00V")
      )
      (libsource (lib "API") (part "RS/ERJ6GEYJ"))
    )
    (comp (ref "R30")
      (value "100K")
      (footprint "R0805")
      (description "RES 100K OHM 1/8W 1% 0805 SMD")
      (fields
        (field (name "MANUFACTURER") "Panasonic - ECG")
        (field (name "MANUFACTURER PART NUMBER") "RC0805JR-07100KL")
      )
      (libsource (lib "API") (part "RS/ERJ6ENF"))
    )
    (comp (ref "R40")
      (value "1.0k 1%")
      (footprint "R0805")
      (description "RES 1.00K OHM 1/8W 1% 0805 SMD")
      (fields
        (field (name "MANUFACTURER") "Yageo")
        (field (name "MANUFACTURER PART NUMBER") "RC0805FR-071KL")
      )
      (libsource (lib "API") (part "RS/ERJ6ENF"))
    )
    (comp (ref "R46")
      (value "15.0 OHM 1%")
      (footprint "R1206")
      (description "RES 15.0 OHM 1/4W 1% 1206 SMD")
      (fields
        (field (name "MANUFACTURER") "Panasonic - ECG")
        (field (name "MANUFACTURER PART NUMBER") "ERJ-8ENF15R0V")
      )
      (libsource (lib "API") (part "RS/ERJ8ENF"))
    )
    (comp (ref "R47")
      (value "15.0 OHM 1%")
      (footprint "R1206")
      (description "RES 15.0 OHM 1/4W 1% 1206 SMD")
      (fields
        (field (name "MANUFACTURER") "Panasonic - ECG")
        (field (name "MANUFACTURER PART NUMBER") "ERJ-8ENF15R0V")
      )
      (libsource (lib "API") (part "RS/ERJ8ENF"))
    )
    (comp (ref "R48")
      (value "15.0 OHM 1%")
      (footprint "R1206")
      (description "RES 15.0 OHM 1/4W 1% 1206 SMD")
      (fields
        (field (name "MANUFACTURER") "Panasonic - ECG")
        (field (name "MANUFACTURER PART NUMBER") "ERJ-8ENF15R0V")
      )
      (libsource (lib "API") (part "RS/ERJ8ENF"))
    )
    (comp (ref "R49")
      (value "15.0 OHM 1%")
      (footprint "R1206")
      (description "RES 15.0 OHM 1/4W 1% 1206 SMD")
      (fields
        (field (name "MANUFACTURER") "Panasonic - ECG")
        (field (name "MANUFACTURER PART NUMBER") "ERJ-8ENF15R0V")
      )
      (libsource (lib "API") (part "RS/ERJ8ENF"))
    )
    (comp (ref "R50")
      (value "15.0 OHM 1%")
      (footprint "R1206")
      (description "RES 15.0 OHM 1/4W 1% 1206 SMD")
      (fields
        (field (name "MANUFACTURER") "Panasonic - ECG")
        (field (name "MANUFACTURER PART NUMBER") "ERJ-8ENF15R0V")
      )
      (libsource (lib "API") (part "RS/ERJ8ENF"))
    )
    (comp (ref "R51")
      (value "15.0 OHM 1%")
      (footprint "R1206")
      (description "RES 15.0 OHM 1/4W 1% 1206 SMD")
      (fields
        (field (name "MANUFACTURER") "Panasonic - ECG")
        (field (name "MANUFACTURER PART NUMBER") "ERJ-8ENF15R0V")
      )
      (libsource (lib "API") (part "RS/ERJ8ENF"))
    )
    (comp (ref "R52")
      (value "15.0 OHM 1%")
      (footprint "R1206")
      (description "RES 15.0 OHM 1/4W 1% 1206 SMD")
      (fields
        (field (name "MANUFACTURER") "Panasonic - ECG")
        (field (name "MANUFACTURER PART NUMBER") "ERJ-8ENF15R0V")
      )
      (libsource (lib "API") (part "RS/ERJ8ENF"))
    )
    (comp (ref "R53")
      (value "15.0 OHM 1%")
      (footprint "R1206")
      (description "RES 15.0 OHM 1/4W 1% 1206 SMD")
      (fields
        (field (name "MANUFACTURER") "Panasonic - ECG")
        (field (name "MANUFACTURER PART NUMBER") "ERJ-8ENF15R0V")
      )
      (libsource (lib "API") (part "RS/ERJ8ENF"))
    )
    (comp (ref "R54")
      (value "15.0 OHM 1%")
      (footprint "R1206")
      (description "RES 15.0 OHM 1/4W 1% 1206 SMD")
      (fields
        (field (name "MANUFACTURER") "Panasonic - ECG")
        (field (name "MANUFACTURER PART NUMBER") "ERJ-8ENF15R0V")
      )
      (libsource (lib "API") (part "RS/ERJ8ENF"))
    )
    (comp (ref "R55")
      (value "15.0 OHM 1%")
      (footprint "R1206")
      (description "RES 15.0 OHM 1/4W 1% 1206 SMD")
      (fields
        (field (name "MANUFACTURER") "Panasonic - ECG")
        (field (name "MANUFACTURER PART NUMBER") "ERJ-8ENF15R0V")
      )
      (libsource (lib "API") (part "RS/ERJ8ENF"))
    )
    (comp (ref "R56")
      (value "15.0 OHM 1%")
      (footprint "R1206")
      (description "RES 15.0 OHM 1/4W 1% 1206 SMD")
      (fields
        (field (name "MANUFACTURER") "Panasonic - ECG")
        (field (name "MANUFACTURER PART NUMBER") "ERJ-8ENF15R0V")
      )
      (libsource (lib "API") (part "RS/ERJ8ENF"))
    )
    (comp (ref "R57")
      (value "15.0 OHM 1%")
      (footprint "R1206")
      (description "RES 15.0 OHM 1/4W 1% 1206 SMD")
      (fields
        (field (name "MANUFACTURER") "Panasonic - ECG")
        (field (name "MANUFACTURER PART NUMBER") "ERJ-8ENF15R0V")
      )
      (libsource (lib "API") (part "RS/ERJ8ENF"))
    )
    (comp (ref "R58")
      (value "32.4 OHM 1%")
      (footprint "R1206")
      (description "RES 32.4 OHM 1/4W 1% 1206 SMD")
      (fields
        (field (name "MANUFACTURER") "Panasonic - ECG")
        (field (name "MANUFACTURER PART NUMBER") "ERJ-8ENF32R4V")
      )
      (libsource (lib "API") (part "RS/ERJ8ENF"))
    )
    (comp (ref "R59")
      (value "32.4 OHM 1%")
      (footprint "R1206")
      (description "RES 32.4 OHM 1/4W 1% 1206 SMD")
      (fields
        (field (name "MANUFACTURER") "Panasonic - ECG")
        (field (name "MANUFACTURER PART NUMBER") "ERJ-8ENF32R4V")
      )
      (libsource (lib "API") (part "RS/ERJ8ENF"))
    )
    (comp (ref "R60")
      (value "32.4 OHM 1%")
      (footprint "R1206")
      (description "RES 32.4 OHM 1/4W 1% 1206 SMD")
      (fields
        (field (name "MANUFACTURER") "Panasonic - ECG")
        (field (name "MANUFACTURER PART NUMBER") "ERJ-8ENF32R4V")
      )
      (libsource (lib "API") (part "RS/ERJ8ENF"))
    )
    (comp (ref "R61")
      (value "32.4 OHM 1%")
      (footprint "R1206")
      (description "RES 32.4 OHM 1/4W 1% 1206 SMD")
      (fields
        (field (name "MANUFACTURER") "Panasonic - ECG")
        (field (name "MANUFACTURER PART NUMBER") "ERJ-8ENF32R4V")
      )
      (libsource (lib "API") (part "RS/ERJ8ENF"))
    )
    (comp (ref "R62")
      (value "32.4 OHM 1%")
      (footprint "R1206")
      (description "RES 32.4 OHM 1/4W 1% 1206 SMD")
      (fields
        (field (name "MANUFACTURER") "Panasonic - ECG")
        (field (name "MANUFACTURER PART NUMBER") "ERJ-8ENF32R4V")
      )
      (libsource (lib "API") (part "RS/ERJ8ENF"))
    )
    (comp (ref "R63")
      (value "32.4 OHM 1%")
      (footprint "R1206")
      (description "RES 32.4 OHM 1/4W 1% 1206 SMD")
      (fields
        (field (name "MANUFACTURER") "Panasonic - ECG")
        (field (name "MANUFACTURER PART NUMBER") "ERJ-8ENF32R4V")
      )
      (libsource (lib "API") (part "RS/ERJ8ENF"))
    )
    (comp (ref "R64")
      (value "32.4 OHM 1%")
      (footprint "R1206")
      (description "RES 32.4 OHM 1/4W 1% 1206 SMD")
      (fields
        (field (name "MANUFACTURER") "Panasonic - ECG")
        (field (name "MANUFACTURER PART NUMBER") "ERJ-8ENF32R4V")
      )
      (libsource (lib "API") (part "RS/ERJ8ENF"))
    )
    (comp (ref "R65")
      (value "32.4 OHM 1%")
      (footprint "R1206")
      (description "RES 32.4 OHM 1/4W 1% 1206 SMD")
      (fields
        (field (name "MANUFACTURER") "Panasonic - ECG")
        (field (name "MANUFACTURER PART NUMBER") "ERJ-8ENF32R4V")
      )
      (libsource (lib "API") (part "RS/ERJ8ENF"))
    )
    (comp (ref "R66")
      (value "32.4 OHM 1%")
      (footprint "R1206")
      (description "RES 32.4 OHM 1/4W 1% 1206 SMD")
      (fields
        (field (name "MANUFACTURER") "Panasonic - ECG")
        (field (name "MANUFACTURER PART NUMBER") "ERJ-8ENF32R4V")
      )
      (libsource (lib "API") (part "RS/ERJ8ENF"))
    )
    (comp (ref "R67")
      (value "32.4 OHM 1%")
      (footprint "R1206")
      (description "RES 32.4 OHM 1/4W 1% 1206 SMD")
      (fields
        (field (name "MANUFACTURER") "Panasonic - ECG")
        (field (name "MANUFACTURER PART NUMBER") "ERJ-8ENF32R4V")
      )
      (libsource (lib "API") (part "RS/ERJ8ENF"))
    )
    (comp (ref "R68")
      (value "32.4 OHM 1%")
      (footprint "R1206")
      (description "RES 32.4 OHM 1/4W 1% 1206 SMD")
      (fields
        (field (name "MANUFACTURER") "Panasonic - ECG")
        (field (name "MANUFACTURER PART NUMBER") "ERJ-8ENF32R4V")
      )
      (libsource (lib "API") (part "RS/ERJ8ENF"))
    )
    (comp (ref "R69")
      (value "32.4 OHM 1%")
      (footprint "R1206")
      (description "RES 32.4 OHM 1/4W 1% 1206 SMD")
      (fields
        (field (name "MANUFACTURER") "Panasonic - ECG")
        (field (name "MANUFACTURER PART NUMBER") "ERJ-8ENF32R4V")
      )
      (libsource (lib "API") (part "RS/ERJ8ENF"))
    )
    (comp (ref "R88")
      (value "15.0 OHM 1%")
      (footprint "R1206")
      (description "RES 15.0 OHM 1/4W 1% 1206 SMD")
      (fields
        (field (name "MANUFACTURER") "Panasonic - ECG")
        (field (name "MANUFACTURER PART NUMBER") "ERJ-8ENF15R0V")
      )
      (libsource (lib "API") (part "RS/ERJ8ENF"))
    )
    (comp (ref "R89")
      (value "15.0 OHM 1%")
      (footprint "R1206")
      (description "RES 15.0 OHM 1/4W 1% 1206 SMD")
      (fields
        (field (name "MANUFACTURER") "Panasonic - ECG")
        (field (name "MANUFACTURER PART NUMBER") "ERJ-8ENF15R0V")
      )
      (libsource (lib "API") (part "RS/ERJ8ENF"))
    )
    (comp (ref "R90")
      (value "15.0 OHM 1%")
      (footprint "R1206")
      (description "RES 15.0 OHM 1/4W 1% 1206 SMD")
      (fields
        (field (name "MANUFACTURER") "Panasonic - ECG")
        (field (name "MANUFACTURER PART NUMBER") "ERJ-8ENF15R0V")
      )
      (libsource (lib "API") (part "RS/ERJ8ENF"))
    )
    (comp (ref "R91")
      (value "15.0 OHM 1%")
      (footprint "R1206")
      (description "RES 15.0 OHM 1/4W 1% 1206 SMD")
      (fields
        (field (name "MANUFACTURER") "Panasonic - ECG")
        (field (name "MANUFACTURER PART NUMBER") "ERJ-8ENF15R0V")
      )
      (libsource (lib "API") (part "RS/ERJ8ENF"))
    )
    (comp (ref "R92")
      (value "15.0 OHM 1%")
      (footprint "R1206")
      (description "RES 15.0 OHM 1/4W 1% 1206 SMD")
      (fields
        (field (name "MANUFACTURER") "Panasonic - ECG")
        (field (name "MANUFACTURER PART NUMBER") "ERJ-8ENF15R0V")
      )
      (libsource (lib "API") (part "RS/ERJ8ENF"))
    )
    (comp (ref "R93")
      (value "15.0 OHM 1%")
      (footprint "R1206")
      (description "RES 15.0 OHM 1/4W 1% 1206 SMD")
      (fields
        (field (name "MANUFACTURER") "Panasonic - ECG")
        (field (name "MANUFACTURER PART NUMBER") "ERJ-8ENF15R0V")
      )
      (libsource (lib "API") (part "RS/ERJ8ENF"))
    )
    (comp (ref "R94")
      (value "15.0 OHM 1%")
      (footprint "R1206")
      (description "RES 15.0 OHM 1/4W 1% 1206 SMD")
      (fields
        (field (name "MANUFACTURER") "Panasonic - ECG")
        (field (name "MANUFACTURER PART NUMBER") "ERJ-8ENF15R0V")
      )
      (libsource (lib "API") (part "RS/ERJ8ENF"))
    )
    (comp (ref "R95")
      (value "15.0 OHM 1%")
      (footprint "R1206")
      (description "RES 15.0 OHM 1/4W 1% 1206 SMD")
      (fields
        (field (name "MANUFACTURER") "Panasonic - ECG")
        (field (name "MANUFACTURER PART NUMBER") "ERJ-8ENF15R0V")
      )
      (libsource (lib "API") (part "RS/ERJ8ENF"))
    )
    (comp (ref "R96")
      (value "15.0 OHM 1%")
      (footprint "R1206")
      (description "RES 15.0 OHM 1/4W 1% 1206 SMD")
      (fields
        (field (name "MANUFACTURER") "Panasonic - ECG")
        (field (name "MANUFACTURER PART NUMBER") "ERJ-8ENF15R0V")
      )
      (libsource (lib "API") (part "RS/ERJ8ENF"))
    )
    (comp (ref "R97")
      (value "15.0 OHM 1%")
      (footprint "R1206")
      (description "RES 15.0 OHM 1/4W 1% 1206 SMD")
      (fields
        (field (name "MANUFACTURER") "Panasonic - ECG")
        (field (name "MANUFACTURER PART NUMBER") "ERJ-8ENF15R0V")
      )
      (libsource (lib "API") (part "RS/ERJ8ENF"))
    )
    (comp (ref "R98")
      (value "15.0 OHM 1%")
      (footprint "R1206")
      (description "RES 15.0 OHM 1/4W 1% 1206 SMD")
      (fields
        (field (name "MANUFACTURER") "Panasonic - ECG")
        (field (name "MANUFACTURER PART NUMBER") "ERJ-8ENF15R0V")
      )
      (libsource (lib "API") (part "RS/ERJ8ENF"))
    )
    (comp (ref "R99")
      (value "15.0 OHM 1%")
      (footprint "R1206")
      (description "RES 15.0 OHM 1/4W 1% 1206 SMD")
      (fields
        (field (name "MANUFACTURER") "Panasonic - ECG")
        (field (name "MANUFACTURER PART NUMBER") "ERJ-8ENF15R0V")
      )
      (libsource (lib "API") (part "RS/ERJ8ENF"))
    )
    (comp (ref "R100")
      (value "32.4 OHM 1%")
      (footprint "R1206")
      (description "RES 32.4 OHM 1/4W 1% 1206 SMD")
      (fields
        (field (name "MANUFACTURER") "Panasonic - ECG")
        (field (name "MANUFACTURER PART NUMBER") "ERJ-8ENF32R4V")
      )
      (libsource (lib "API") (part "RS/ERJ8ENF"))
    )
    (comp (ref "R101")
      (value "32.4 OHM 1%")
      (footprint "R1206")
      (description "RES 32.4 OHM 1/4W 1% 1206 SMD")
      (fields
        (field (name "MANUFACTURER") "Panasonic - ECG")
        (field (name "MANUFACTURER PART NUMBER") "ERJ-8ENF32R4V")
      )
      (libsource (lib "API") (part "RS/ERJ8ENF"))
    )
    (comp (ref "R102")
      (value "32.4 OHM 1%")
      (footprint "R1206")
      (description "RES 32.4 OHM 1/4W 1% 1206 SMD")
      (fields
        (field (name "MANUFACTURER") "Panasonic - ECG")
        (field (name "MANUFACTURER PART NUMBER") "ERJ-8ENF32R4V")
      )
      (libsource (lib "API") (part "RS/ERJ8ENF"))
    )
    (comp (ref "R103")
      (value "32.4 OHM 1%")
      (footprint "R1206")
      (description "RES 32.4 OHM 1/4W 1% 1206 SMD")
      (fields
        (field (name "MANUFACTURER") "Panasonic - ECG")
        (field (name "MANUFACTURER PART NUMBER") "ERJ-8ENF32R4V")
      )
      (libsource (lib "API") (part "RS/ERJ8ENF"))
    )
    (comp (ref "R104")
      (value "32.4 OHM 1%")
      (footprint "R1206")
      (description "RES 32.4 OHM 1/4W 1% 1206 SMD")
      (fields
        (field (name "MANUFACTURER") "Panasonic - ECG")
        (field (name "MANUFACTURER PART NUMBER") "ERJ-8ENF32R4V")
      )
      (libsource (lib "API") (part "RS/ERJ8ENF"))
    )
    (comp (ref "R105")
      (value "32.4 OHM 1%")
      (footprint "R1206")
      (description "RES 32.4 OHM 1/4W 1% 1206 SMD")
      (fields
        (field (name "MANUFACTURER") "Panasonic - ECG")
        (field (name "MANUFACTURER PART NUMBER") "ERJ-8ENF32R4V")
      )
      (libsource (lib "API") (part "RS/ERJ8ENF"))
    )
    (comp (ref "R106")
      (value "32.4 OHM 1%")
      (footprint "R1206")
      (description "RES 32.4 OHM 1/4W 1% 1206 SMD")
      (fields
        (field (name "MANUFACTURER") "Panasonic - ECG")
        (field (name "MANUFACTURER PART NUMBER") "ERJ-8ENF32R4V")
      )
      (libsource (lib "API") (part "RS/ERJ8ENF"))
    )
    (comp (ref "R107")
      (value "32.4 OHM 1%")
      (footprint "R1206")
      (description "RES 32.4 OHM 1/4W 1% 1206 SMD")
      (fields
        (field (name "MANUFACTURER") "Panasonic - ECG")
        (field (name "MANUFACTURER PART NUMBER") "ERJ-8ENF32R4V")
      )
      (libsource (lib "API") (part "RS/ERJ8ENF"))
    )
    (comp (ref "R108")
      (value "32.4 OHM 1%")
      (footprint "R1206")
      (description "RES 32.4 OHM 1/4W 1% 1206 SMD")
      (fields
        (field (name "MANUFACTURER") "Panasonic - ECG")
        (field (name "MANUFACTURER PART NUMBER") "ERJ-8ENF32R4V")
      )
      (libsource (lib "API") (part "RS/ERJ8ENF"))
    )
    (comp (ref "R109")
      (value "32.4 OHM 1%")
      (footprint "R1206")
      (description "RES 32.4 OHM 1/4W 1% 1206 SMD")
      (fields
        (field (name "MANUFACTURER") "Panasonic - ECG")
        (field (name "MANUFACTURER PART NUMBER") "ERJ-8ENF32R4V")
      )
      (libsource (lib "API") (part "RS/ERJ8ENF"))
    )
    (comp (ref "R110")
      (value "32.4 OHM 1%")
      (footprint "R1206")
      (description "RES 32.4 OHM 1/4W 1% 1206 SMD")
      (fields
        (field (name "MANUFACTURER") "Panasonic - ECG")
        (field (name "MANUFACTURER PART NUMBER") "ERJ-8ENF32R4V")
      )
      (libsource (lib "API") (part "RS/ERJ8ENF"))
    )
    (comp (ref "R111")
      (value "32.4 OHM 1%")
      (footprint "R1206")
      (description "RES 32.4 OHM 1/4W 1% 1206 SMD")
      (fields
        (field (name "MANUFACTURER") "Panasonic - ECG")
        (field (name "MANUFACTURER PART NUMBER") "ERJ-8ENF32R4V")
      )
      (libsource (lib "API") (part "RS/ERJ8ENF"))
    )
    (comp (ref "R112")
      (value "10.0k")
      (footprint "R0805")
      (description "RES 10.0K OHM 1/8W 1% 0805 SMD")
      (fields
        (field (name "MANUFACTURER") "Panasonic - ECG")
        (field (name "MANUFACTURER PART NUMBER") "ERJ-6ENF1002V")
      )
      (libsource (lib "API") (part "RS/ERJ6ENF"))
    )
    (comp (ref "R128")
      (value "3.16K")
      (footprint "R0805")
      (description "RES 3.16K OHM 1/8W 1% 0805 SMD")
      (fields
        (field (name "MANUFACTURER") "Panasonic - ECG")
        (field (name "MANUFACTURER PART NUMBER") "ERJ-6ENF3161V")
      )
      (libsource (lib "API") (part "RS/ERJ6ENF"))
    )
    (comp (ref "R129")
      (value "20.0k")
      (footprint "R0805")
      (description "RES 20.0K OHM 1/8W 1% 0805 SMD")
      (fields
        (field (name "MANUFACTURER") "Panasonic - ECG")
        (field (name "MANUFACTURER PART NUMBER") "ERJ-6ENF2002V")
      )
      (libsource (lib "API") (part "RS/ERJ6ENF"))
    )
    (comp (ref "R130")
      (value "10.0k")
      (footprint "R0805")
      (description "RES 10.0K OHM 1/8W 1% 0805 SMD")
      (fields
        (field (name "MANUFACTURER") "Panasonic - ECG")
        (field (name "MANUFACTURER PART NUMBER") "ERJ-6ENF1002V")
      )
      (libsource (lib "API") (part "RS/ERJ6ENF"))
    )
    (comp (ref "U1")
      (value "M25P64-VMF6G")
      (footprint "so16w")
      (description "64 MBit Serial SPI NOR FLASH")
      (fields
        (field (name "MANUFACTURER") "STMicroelectronics / Numonyx")
        (field (name "MANUFACTURER PART NUMBER") "M25P64-VMF6P")
      )
      (libsource (lib "API") (part "IS/M25P64VMF6GZ"))
    )
    (comp (ref "U2")
      (value "dsPIC30F5013-20I/PT")
      (footprint "TQFP-80")
      (description "IC DSPIC MCU/DSP 144K 80TQFP")
      (fields
        (field (name "MANUFACTURER") "Microchip Technology")
        (field (name "MANUFACTURER PART NUMBER") "DSPIC30F6014A-30I/PT")
      )
      (libsource (lib "API") (part "IS/DSPIC30F501320IPTZ_1"))
    )
    (comp (ref "U3")
      (value "SN65HVD230DR")
      (footprint "SOIC 8")
      (description "IC 3.3V CAN TXRX W/STNDBY 8-SOIC")
      (fields (field (name "MANUFACTURER") "Texas Instruments"))
      (libsource (lib "API") (part "IS/SN65HVD230DRT"))
    )
    (comp (ref "U4")
      (value "M25P64-VMF6G")
      (footprint "so16w")
      (description "64 MBit Serial SPI NOR FLASH")
      (fields
        (field (name "MANUFACTURER") "STMicroelectronics / Numonyx")
        (field (name "MANUFACTURER PART NUMBER") "M25P64-VMF6P")
      )
      (libsource (lib "API") (part "IS/M25P64VMF6GZ"))
    )
    (comp (ref "U5")
      (value "CS4344-CZZ")
      (footprint "TSSOP\\10")
      (description "IC DAC 24BIT 192KHZ 10-TSSOP")
      (fields (field (name "MANUFACTURER") "Cirrus Logic Inc"))
      (libsource (lib "API") (part "IS/CS4344CZZZ"))
    )
    (comp (ref "U6")
      (value "LM2676S-ADJ/NOPB")
      (footprint "TO263\\7")
      (description "NATIONAL SEMICONDUCTOR - LM2676S-ADJ/NOPB - IC, STEP-DOWN REGULATOR, TO-263-7")
      (fields (field (name "MANUFACTURER") "NATIONAL SEMICONDUCTOR"))
      (libsource (lib "ELC0103 - Master & ELC0104 - Slave") (part "IS/LM2676SADJN"))
    )
    (comp (ref "U7")
      (value "LP2950CDT-3.3")
      (footprint "D-PAK / TO-252AA")
      (description "IC REG VOLT MICROPWR 3.3V TO-252")
      (fields
        (field (name "MANUFACTURER") "National Semiconductor")
        (field (name "MANUFACTURER PART NUMBER") "LP2950CDT-3.3/NOPB")
      )
      (libsource (lib "API") (part "IS/LP2950CDT33N"))
    )
    (comp (ref "U8")
      (value "M25P64-VMF6G")
      (footprint "so16w")
      (description "64 MBit Serial SPI NOR FLASH")
      (fields
        (field (name "MANUFACTURER") "STMicroelectronics / Numonyx")
        (field (name "MANUFACTURER PART NUMBER") "M25P64-VMF6P")
      )
      (libsource (lib "API") (part "IS/M25P64VMF6GZ"))
    )
    (comp (ref "U9")
      (value "M25P64-VMF6G")
      (footprint "so16w")
      (description "64 MBit Serial SPI NOR FLASH")
      (fields
        (field (name "MANUFACTURER") "STMicroelectronics / Numonyx")
        (field (name "MANUFACTURER PART NUMBER") "M25P64-VMF6P")
      )
      (libsource (lib "API") (part "IS/M25P64VMF6GZ"))
    )
    (comp (ref "U10")
      (value "LM4861M")
      (footprint "M08A")
      (description "IC AMP AUDIO PWR W/SHUTDN 8-SOIC")
      (fields (field (name "MANUFACTURER") "National Semiconductor"))
      (libsource (lib "NSC Audio Power Amplifier") (part "LM4861M"))
    )
    (comp (ref "U11")
      (value "LM2676S-ADJ/NOPB")
      (footprint "TO263\\7")
      (description "NATIONAL SEMICONDUCTOR - LM2676S-ADJ/NOPB - IC, STEP-DOWN REGULATOR, TO-263-7")
      (fields (field (name "MANUFACTURER") "NATIONAL SEMICONDUCTOR"))
      (libsource (lib "ELC0103 - Master & ELC0104 - Slave") (part "IS/LM2676SADJN"))
    )
    (comp (ref "U12")
      (value "MOCD207M")
      (footprint "SOIC 8")
      (description "OPTOCOUPLER TRANS-OUT 2CH 8-SOIC")
      (fields (field (name "MANUFACTURER") "Fairchild Optoelectronics Group"))
      (libsource (lib "API") (part "I#S/MOCD207MZ"))
    )
    (comp (ref "U13")
      (value "SN74AHC1G125DBVR")
      (footprint "API:SOT23-5")
      (description "TI Tri State Buffer Single Gate")
      (fields (field (name "MANUFACTURER") "Texas Instruments"))
      (libsource (lib "API") (part "I#S/SN74AHC1G125DBVT"))
    )
    (comp (ref "U14")
      (value "IC USB-TO-UART BRIDGE 28MLP")
      (footprint "QFN-28")
      (fields
        (field (name "MANUFACTURER") "Silicon Laboratories Inc")
        (field (name "MANUFACTURER PART NUMBER") "CP2102-GM")
      )
      (libsource (lib "Playworld") (part "CP2102"))
    )
    (comp (ref "Y1")
      (value "8.192MHz")
      (footprint "XTSL\\CSM-7")
      (description "CRYSTAL 8.192MHZ 18PF FUND SMD")
      (fields
        (field (name "MANUFACTURER") "Abracon Corporation")
        (field (name "MANUFACTURER PART NUMBER") "ABLS-8.192MHZ-B2-T")
      )
      (libsource (lib "API") (part "ZS/ECS1228205PTRZ"))
    )
  )
  (nets
    (net (code "1") (name "/5V") (class "Default")
      (node (ref "C18") (pin "1") (pinfunction "1_1") (pintype "passive"))
      (node (ref "C22") (pin "1") (pinfunction "1_1") (pintype "passive"))
      (node (ref "C32") (pin "1") (pinfunction "1_1") (pintype "passive"))
      (node (ref "DS11") (pin "2") (pinfunction "A_2") (pintype "passive"))
      (node (ref "DS12") (pin "2") (pinfunction "A_2") (pintype "passive"))
      (node (ref "DS15") (pin "2") (pinfunction "A_2") (pintype "passive"))
      (node (ref "DS16") (pin "2") (pinfunction "A_2") (pintype "passive"))
      (node (ref "DS19") (pin "2") (pinfunction "A_2") (pintype "passive"))
      (node (ref "DS20") (pin "2") (pinfunction "A_2") (pintype "passive"))
      (node (ref "DS23") (pin "2") (pinfunction "A_2") (pintype "passive"))
      (node (ref "DS24") (pin "2") (pinfunction "A_2") (pintype "passive"))
      (node (ref "DS27") (pin "2") (pinfunction "A_2") (pintype "passive"))
      (node (ref "DS28") (pin "2") (pinfunction "A_2") (pintype "passive"))
      (node (ref "DS3") (pin "2") (pinfunction "A_2") (pintype "passive"))
      (node (ref "DS31") (pin "2") (pinfunction "A_2") (pintype "passive"))
      (node (ref "DS32") (pin "2") (pinfunction "A_2") (pintype "passive"))
      (node (ref "DS35") (pin "2") (pinfunction "A_2") (pintype "passive"))
      (node (ref "DS36") (pin "2") (pinfunction "A_2") (pintype "passive"))
      (node (ref "DS39") (pin "2") (pinfunction "A_2") (pintype "passive"))
      (node (ref "DS4") (pin "2") (pinfunction "A_2") (pintype "passive"))
      (node (ref "DS40") (pin "2") (pinfunction "A_2") (pintype "passive"))
      (node (ref "DS43") (pin "2") (pinfunction "A_2") (pintype "passive"))
      (node (ref "DS44") (pin "2") (pinfunction "A_2") (pintype "passive"))
      (node (ref "DS47") (pin "2") (pinfunction "A_2") (pintype "passive"))
      (node (ref "DS48") (pin "2") (pinfunction "A_2") (pintype "passive"))
      (node (ref "DS7") (pin "2") (pinfunction "A_2") (pintype "passive"))
      (node (ref "DS8") (pin "2") (pinfunction "A_2") (pintype "passive"))
      (node (ref "L1") (pin "2") (pinfunction "2_2") (pintype "passive"))
      (node (ref "R9") (pin "2") (pinfunction "2_2") (pintype "passive"))
      (node (ref "U10") (pin "6") (pinfunction "VDD_6") (pintype "power_in"))
    )
    (net (code "2") (name "/5V_DISABLE") (class "Default")
      (node (ref "R130") (pin "1") (pinfunction "1_1") (pintype "passive"))
      (node (ref "R20") (pin "1") (pinfunction "1_1") (pintype "passive"))
      (node (ref "U2") (pin "35") (pinfunction "AN14/RB14_35") (pintype "bidirectional"))
    )
    (net (code "3") (name "/AUDIO_SHUTDOWN") (class "Default")
      (node (ref "R15") (pin "1") (pinfunction "1_1") (pintype "passive"))
      (node (ref "U10") (pin "1") (pinfunction "SD_1") (pintype "input"))
      (node (ref "U13") (pin "1") (pinfunction "~{OE}_1") (pintype "input"))
      (node (ref "U2") (pin "46") (pinfunction "SDA/RG3_46") (pintype "bidirectional"))
    )
    (net (code "4") (name "/CANRX") (class "Default")
      (node (ref "U2") (pin "72") (pinfunction "C1RX/RF0_72") (pintype "bidirectional"))
      (node (ref "U3") (pin "4") (pinfunction "R_4") (pintype "output"))
    )
    (net (code "5") (name "/CANTX") (class "Default")
      (node (ref "U2") (pin "73") (pinfunction "C1TX/RF1_73") (pintype "bidirectional"))
      (node (ref "U3") (pin "1") (pinfunction "D_1") (pintype "input"))
    )
    (net (code "6") (name "/CAN_~{HS}{slash}STBY") (class "Default")
      (node (ref "U2") (pin "34") (pinfunction "AN13/RB13_34") (pintype "bidirectional"))
      (node (ref "U3") (pin "8") (pinfunction "~{HS}/STBY_8") (pintype "input"))
    )
    (net (code "7") (name "/COFS") (class "Default")
      (node (ref "U2") (pin "1") (pinfunction "COFS/RG15_1") (pintype "bidirectional"))
      (node (ref "U5") (pin "3") (pinfunction "LRCLK_3") (pintype "passive"))
    )
    (net (code "8") (name "/CSCK") (class "Default")
      (node (ref "U2") (pin "78") (pinfunction "CSCK/RG14_78") (pintype "bidirectional"))
      (node (ref "U5") (pin "2") (pinfunction "~{DEM}/SCLK_2") (pintype "passive"))
    )
    (net (code "9") (name "/CSDO") (class "Default")
      (node (ref "U2") (pin "80") (pinfunction "CSDO/RG13_80") (pintype "bidirectional"))
      (node (ref "U5") (pin "1") (pinfunction "SDIN_1") (pintype "passive"))
    )
    (net (code "10") (name "/LED0") (class "Default")
      (node (ref "R28") (pin "1") (pinfunction "1_1") (pintype "passive"))
      (node (ref "U2") (pin "58") (pinfunction "EMUC2/OC1/RD0_58") (pintype "bidirectional"))
    )
    (net (code "11") (name "/LED1") (class "Default")
      (node (ref "R40") (pin "1") (pinfunction "1_1") (pintype "passive"))
      (node (ref "U2") (pin "61") (pinfunction "EMUD2/OC2/RD1_61") (pintype "bidirectional"))
    )
    (net (code "12") (name "/MCLK") (class "Default")
      (node (ref "R29") (pin "2") (pinfunction "2_2") (pintype "passive"))
      (node (ref "R30") (pin "1") (pinfunction "1_1") (pintype "passive"))
      (node (ref "U13") (pin "4") (pinfunction "Y_4") (pintype "output"))
      (node (ref "U5") (pin "4") (pinfunction "MCLK_4") (pintype "passive"))
    )
    (net (code "13") (name "/MCLR") (class "Default")
      (node (ref "J14") (pin "1") (pinfunction "1_1") (pintype "passive"))
      (node (ref "R4") (pin "1") (pinfunction "1_1") (pintype "passive"))
      (node (ref "U2") (pin "9") (pinfunction "~{MCLR}_9") (pintype "input"))
    )
    (net (code "14") (name "/MEM_~{W}") (class "Default")
      (node (ref "R1") (pin "2") (pinfunction "2_2") (pintype "passive"))
      (node (ref "U1") (pin "9") (pinfunction "~{W}/VPP_9") (pintype "input"))
      (node (ref "U2") (pin "36") (pinfunction "AN15/OCFB/CN12/RB15_36") (pintype "bidirectional"))
      (node (ref "U4") (pin "9") (pinfunction "~{W}/VPP_9") (pintype "input"))
      (node (ref "U8") (pin "9") (pinfunction "~{W}/VPP_9") (pintype "input"))
      (node (ref "U9") (pin "9") (pinfunction "~{W}/VPP_9") (pintype "input"))
    )
    (net (code "15") (name "/OPTION0") (class "Default")
      (node (ref "JP4") (pin "1") (pinfunction "1_1") (pintype "passive"))
      (node (ref "R27") (pin "1") (pinfunction "1_1") (pintype "passive"))
      (node (ref "U2") (pin "76") (pinfunction "CN22/RA6_76") (pintype "bidirectional"))
    )
    (net (code "16") (name "/OPTION1") (class "Default")
      (node (ref "JP3") (pin "1") (pinfunction "1_1") (pintype "passive"))
      (node (ref "R26") (pin "1") (pinfunction "1_1") (pintype "passive"))
      (node (ref "U2") (pin "77") (pinfunction "CN23/RA7_77") (pintype "bidirectional"))
    )
    (net (code "17") (name "/OPTION2") (class "Default")
      (node (ref "JP2") (pin "1") (pinfunction "1_1") (pintype "passive"))
      (node (ref "R23") (pin "1") (pinfunction "1_1") (pintype "passive"))
      (node (ref "U2") (pin "23") (pinfunction "VREF-/RA9_23") (pintype "bidirectional"))
    )
    (net (code "18") (name "/OPTION3") (class "Default")
      (node (ref "JP1") (pin "1") (pinfunction "1_1") (pintype "passive"))
      (node (ref "R19") (pin "1") (pinfunction "1_1") (pintype "passive"))
      (node (ref "U2") (pin "24") (pinfunction "VREF+/RA10_24") (pintype "bidirectional"))
    )
    (net (code "19") (name "/PGC") (class "Default")
      (node (ref "J14") (pin "5") (pinfunction "5_5") (pintype "passive"))
      (node (ref "U2") (pin "19") (pinfunction "AN1/CN3/RB1_19") (pintype "bidirectional"))
    )
    (net (code "20") (name "/PGD") (class "Default")
      (node (ref "J14") (pin "4") (pinfunction "4_4") (pintype "passive"))
      (node (ref "U2") (pin "20") (pinfunction "AN0/CN2/RB0_20") (pintype "bidirectional"))
    )
    (net (code "21") (name "/PIEZO_INPUT") (class "Default")
      (node (ref "R129") (pin "1") (pinfunction "1_1") (pintype "passive"))
      (node (ref "R22") (pin "2") (pinfunction "2_2") (pintype "passive"))
      (node (ref "U12") (pin "8") (pinfunction "8_8") (pintype "passive"))
      (node (ref "U2") (pin "69") (pinfunction "OC8/CN16/RD7_69") (pintype "bidirectional"))
      (node (ref "U2") (pin "74") (pinfunction "C2TX/RG1_74") (pintype "bidirectional"))
    )
    (net (code "22") (name "/RXD2") (class "Default")
      (node (ref "U14") (pin "26") (pinfunction "TXD_26") (pintype "output"))
      (node (ref "U2") (pin "39") (pinfunction "U2RX/CN17/RF4_39") (pintype "bidirectional"))
    )
    (net (code "23") (name "/SCK") (class "Default")
      (node (ref "U1") (pin "16") (pinfunction "CLK_16") (pintype "input"))
      (node (ref "U2") (pin "45") (pinfunction "EMUC3/SCK1/INT0/RF6_45") (pintype "bidirectional"))
      (node (ref "U4") (pin "16") (pinfunction "CLK_16") (pintype "input"))
      (node (ref "U8") (pin "16") (pinfunction "CLK_16") (pintype "input"))
      (node (ref "U9") (pin "16") (pinfunction "CLK_16") (pintype "input"))
    )
    (net (code "24") (name "/SDI") (class "Default")
      (node (ref "R21") (pin "1") (pinfunction "1_1") (pintype "passive"))
      (node (ref "U1") (pin "8") (pinfunction "Q_8") (pintype "tri_state"))
      (node (ref "U2") (pin "44") (pinfunction "SDI1/RF7_44") (pintype "bidirectional"))
      (node (ref "U4") (pin "8") (pinfunction "Q_8") (pintype "tri_state"))
      (node (ref "U8") (pin "8") (pinfunction "Q_8") (pintype "tri_state"))
      (node (ref "U9") (pin "8") (pinfunction "Q_8") (pintype "tri_state"))
    )
    (net (code "25") (name "/SDO") (class "Default")
      (node (ref "U1") (pin "15") (pinfunction "D_15") (pintype "input"))
      (node (ref "U2") (pin "43") (pinfunction "EMUD3/SDO1/RF8_43") (pintype "bidirectional"))
      (node (ref "U4") (pin "15") (pinfunction "D_15") (pintype "input"))
      (node (ref "U8") (pin "15") (pinfunction "D_15") (pintype "input"))
      (node (ref "U9") (pin "15") (pinfunction "D_15") (pintype "input"))
    )
    (net (code "26") (name "/TXD2") (class "Default")
      (node (ref "U14") (pin "25") (pinfunction "RXD_25") (pintype "input"))
      (node (ref "U2") (pin "40") (pinfunction "U2TX/CN18/RF5_40") (pintype "bidirectional"))
    )
    (net (code "27") (name "/USB_RST") (class "Default")
      (node (ref "R112") (pin "1") (pinfunction "1_1") (pintype "passive"))
      (node (ref "U14") (pin "9") (pinfunction "~{RST}_9") (pintype "bidirectional"))
      (node (ref "U2") (pin "75") (pinfunction "C2RX/RG0_75") (pintype "bidirectional"))
    )
    (net (code "28") (name "/VIN_SENSE_ANALOG") (class "Default")
      (node (ref "C37") (pin "1") (pinfunction "1_1") (pintype "passive"))
      (node (ref "R24") (pin "1") (pinfunction "1_1") (pintype "passive"))
      (node (ref "R25") (pin "2") (pinfunction "2_2") (pintype "passive"))
      (node (ref "U2") (pin "18") (pinfunction "AN2/~{SS1}/LVDIN/CN4/RB2_18") (pintype "bidirectional"))
    )
    (net (code "29") (name "/V_IN") (class "Default")
      (node (ref "C10") (pin "1") (pinfunction "1_1") (pintype "passive"))
      (node (ref "C13") (pin "1") (pinfunction "1_1") (pintype "passive"))
      (node (ref "C34") (pin "1") (pinfunction "1_1") (pintype "passive"))
      (node (ref "C5") (pin "1") (pinfunction "1_1") (pintype "passive"))
      (node (ref "C7") (pin "1") (pinfunction "1_1") (pintype "passive"))
      (node (ref "D1") (pin "K") (pinfunction "K_K") (pintype "passive"))
      (node (ref "R24") (pin "2") (pinfunction "2_2") (pintype "passive"))
      (node (ref "U11") (pin "2") (pinfunction "IN_2") (pintype "power_in"))
      (node (ref "U12") (pin "1") (pinfunction "1_1") (pintype "passive"))
      (node (ref "U12") (pin "4") (pinfunction "4_4") (pintype "passive"))
      (node (ref "U6") (pin "2") (pinfunction "IN_2") (pintype "power_in"))
      (node (ref "U7") (pin "1") (pinfunction "IN_1") (pintype "power_in"))
    )
    (net (code "30") (name "/V_RED") (class "Default")
      (node (ref "C30") (pin "1") (pinfunction "1_1") (pintype "passive"))
      (node (ref "C31") (pin "1") (pinfunction "1_1") (pintype "passive"))
      (node (ref "DS1") (pin "2") (pinfunction "A_2") (pintype "passive"))
      (node (ref "DS10") (pin "2") (pinfunction "A_2") (pintype "passive"))
      (node (ref "DS13") (pin "2") (pinfunction "A_2") (pintype "passive"))
      (node (ref "DS14") (pin "2") (pinfunction "A_2") (pintype "passive"))
      (node (ref "DS17") (pin "2") (pinfunction "A_2") (pintype "passive"))
      (node (ref "DS18") (pin "2") (pinfunction "A_2") (pintype "passive"))
      (node (ref "DS2") (pin "2") (pinfunction "A_2") (pintype "passive"))
      (node (ref "DS21") (pin "2") (pinfunction "A_2") (pintype "passive"))
      (node (ref "DS22") (pin "2") (pinfunction "A_2") (pintype "passive"))
      (node (ref "DS25") (pin "2") (pinfunction "A_2") (pintype "passive"))
      (node (ref "DS26") (pin "2") (pinfunction "A_2") (pintype "passive"))
      (node (ref "DS29") (pin "2") (pinfunction "A_2") (pintype "passive"))
      (node (ref "DS30") (pin "2") (pinfunction "A_2") (pintype "passive"))
      (node (ref "DS33") (pin "2") (pinfunction "A_2") (pintype "passive"))
      (node (ref "DS34") (pin "2") (pinfunction "A_2") (pintype "passive"))
      (node (ref "DS37") (pin "2") (pinfunction "A_2") (pintype "passive"))
      (node (ref "DS38") (pin "2") (pinfunction "A_2") (pintype "passive"))
      (node (ref "DS41") (pin "2") (pinfunction "A_2") (pintype "passive"))
      (node (ref "DS42") (pin "2") (pinfunction "A_2") (pintype "passive"))
      (node (ref "DS45") (pin "2") (pinfunction "A_2") (pintype "passive"))
      (node (ref "DS46") (pin "2") (pinfunction "A_2") (pintype "passive"))
      (node (ref "DS5") (pin "2") (pinfunction "A_2") (pintype "passive"))
      (node (ref "DS6") (pin "2") (pinfunction "A_2") (pintype "passive"))
      (node (ref "DS9") (pin "2") (pinfunction "A_2") (pintype "passive"))
      (node (ref "L2") (pin "2") (pinfunction "2_2") (pintype "passive"))
      (node (ref "R18") (pin "2") (pinfunction "2_2") (pintype "passive"))
    )
    (net (code "31") (name "/~{MEM0}") (class "Default")
      (node (ref "R3") (pin "1") (pinfunction "1_1") (pintype "passive"))
      (node (ref "U1") (pin "7") (pinfunction "~{S}_7") (pintype "input"))
      (node (ref "U2") (pin "13") (pinfunction "INT1/RA12_13") (pintype "bidirectional"))
    )
    (net (code "32") (name "/~{MEM1}") (class "Default")
      (node (ref "R6") (pin "1") (pinfunction "1_1") (pintype "passive"))
      (node (ref "U2") (pin "14") (pinfunction "INT2/RA13_14") (pintype "bidirectional"))
      (node (ref "U4") (pin "7") (pinfunction "~{S}_7") (pintype "input"))
    )
    (net (code "33") (name "/~{MEM2}") (class "Default")
      (node (ref "R10") (pin "1") (pinfunction "1_1") (pintype "passive"))
      (node (ref "U2") (pin "52") (pinfunction "INT3/RA14_52") (pintype "bidirectional"))
      (node (ref "U8") (pin "7") (pinfunction "~{S}_7") (pintype "input"))
    )
    (net (code "34") (name "/~{MEM3}") (class "Default")
      (node (ref "R14") (pin "1") (pinfunction "1_1") (pintype "passive"))
      (node (ref "U2") (pin "53") (pinfunction "INT4/RA15_53") (pintype "bidirectional"))
      (node (ref "U9") (pin "7") (pinfunction "~{S}_7") (pintype "input"))
    )
    (net (code "35") (name "GND") (class "Default")
      (node (ref "C1") (pin "2") (pinfunction "2_2") (pintype "passive"))
      (node (ref "C10") (pin "2") (pinfunction "2_2") (pintype "passive"))
      (node (ref "C11") (pin "2") (pinfunction "2_2") (pintype "passive"))
      (node (ref "C13") (pin "2") (pinfunction "2_2") (pintype "passive"))
      (node (ref "C14") (pin "2") (pinfunction "2_2") (pintype "passive"))
      (node (ref "C16") (pin "2") (pinfunction "2_2") (pintype "passive"))
      (node (ref "C17") (pin "2") (pinfunction "2_2") (pintype "passive"))
      (node (ref "C18") (pin "2") (pinfunction "2_2") (pintype "passive"))
      (node (ref "C19") (pin "2") (pinfunction "2_2") (pintype "passive"))
      (node (ref "C2") (pin "2") (pinfunction "2_2") (pintype "passive"))
      (node (ref "C20") (pin "2") (pinfunction "2_2") (pintype "passive"))
      (node (ref "C21") (pin "2") (pinfunction "2_2") (pintype "passive"))
      (node (ref "C22") (pin "2") (pinfunction "2_2") (pintype "passive"))
      (node (ref "C23") (pin "2") (pinfunction "2_2") (pintype "passive"))
      (node (ref "C24") (pin "2") (pinfunction "2_2") (pintype "passive"))
      (node (ref "C28") (pin "2") (pinfunction "2_2") (pintype "passive"))
      (node (ref "C3") (pin "2") (pinfunction "2_2") (pintype "passive"))
      (node (ref "C30") (pin "2") (pinfunction "2_2") (pintype "passive"))
      (node (ref "C31") (pin "2") (pinfunction "2_2") (pintype "passive"))
      (node (ref "C32") (pin "2") (pinfunction "2_2") (pintype "passive"))
      (node (ref "C33") (pin "2") (pinfunction "2_2") (pintype "passive"))
      (node (ref "C34") (pin "2") (pinfunction "2_2") (pintype "passive"))
      (node (ref "C37") (pin "2") (pinfunction "2_2") (pintype "passive"))
      (node (ref "C4") (pin "2") (pinfunction "2_2") (pintype "passive"))
      (node (ref "C42") (pin "2") (pinfunction "2_2") (pintype "passive"))
      (node (ref "C5") (pin "2") (pinfunction "2_2") (pintype "passive"))
      (node (ref "C6") (pin "2") (pinfunction "2_2") (pintype "passive"))
      (node (ref "C7") (pin "2") (pinfunction "2_2") (pintype "passive"))
      (node (ref "C8") (pin "2") (pinfunction "2_2") (pintype "passive"))
      (node (ref "C9") (pin "2") (pinfunction "2_2") (pintype "passive"))
      (node (ref "D2") (pin "3") (pinfunction "A_3") (pintype "passive"))
      (node (ref "D3") (pin "1") (pinfunction "A_1") (pintype "passive"))
      (node (ref "D4") (pin "1") (pinfunction "A_1") (pintype "passive"))
      (node (ref "D5") (pin "1") (pinfunction "A_1") (pintype "passive"))
      (node (ref "D7") (pin "3") (pinfunction "A_3") (pintype "passive"))
      (node (ref "DS49") (pin "2") (pinfunction "K_2") (pintype "passive"))
      (node (ref "DS50") (pin "2") (pinfunction "K_2") (pintype "passive"))
      (node (ref "J1") (pin "1") (pinfunction ".125_AMP-IN_1") (pintype "passive"))
      (node (ref "J12") (pin "1") (pinfunction ".125_AMP-IN_1") (pintype "passive"))
      (node (ref "J13") (pin "4") (pinfunction "GND_4") (pintype "power_in"))
      (node (ref "J14") (pin "3") (pinfunction "3_3") (pintype "passive"))
      (node (ref "J5") (pin "1") (pinfunction ".125_AMP-IN_1") (pintype "passive"))
      (node (ref "JP1") (pin "2") (pinfunction "2_2") (pintype "passive"))
      (node (ref "JP2") (pin "2") (pinfunction "2_2") (pintype "passive"))
      (node (ref "JP3") (pin "2") (pinfunction "2_2") (pintype "passive"))
      (node (ref "JP4") (pin "2") (pinfunction "2_2") (pintype "passive"))
      (node (ref "Q1") (pin "1") (pinfunction "S_1") (pintype "passive"))
      (node (ref "Q1") (pin "2") (pinfunction "S_2") (pintype "passive"))
      (node (ref "Q1") (pin "3") (pinfunction "S_3") (pintype "passive"))
      (node (ref "Q2") (pin "1") (pinfunction "S_1") (pintype "passive"))
      (node (ref "Q2") (pin "2") (pinfunction "S_2") (pintype "passive"))
      (node (ref "Q2") (pin "3") (pinfunction "S_3") (pintype "passive"))
      (node (ref "R11") (pin "1") (pinfunction "1_1") (pintype "passive"))
      (node (ref "R17") (pin "1") (pinfunction "1_1") (pintype "passive"))
      (node (ref "R25") (pin "1") (pinfunction "1_1") (pintype "passive"))
      (node (ref "R7") (pin "1") (pinfunction "1_1") (pintype "passive"))
      (node (ref "U1") (pin "10") (pinfunction "VSS_10") (pintype "power_in"))
      (node (ref "U10") (pin "7") (pinfunction "GND_7") (pintype "power_in"))
      (node (ref "U11") (pin "4") (pinfunction "GND_4") (pintype "power_in"))
      (node (ref "U11") (pin "8") (pinfunction "GND_8") (pintype "power_in"))
      (node (ref "U12") (pin "7") (pinfunction "7_7") (pintype "passive"))
      (node (ref "U13") (pin "3") (pinfunction "GND_3") (pintype "power_in"))
      (node (ref "U14") (pin "29") (pinfunction "THERMAL_PAD_29") (pintype "passive"))
      (node (ref "U14") (pin "3") (pinfunction "GND_3") (pintype "power_in"))
      (node (ref "U2") (pin "11") (pinfunction "VSS_11") (pintype "power_in"))
      (node (ref "U2") (pin "26") (pinfunction "AVSS_26") (pintype "power_in"))
      (node (ref "U2") (pin "31") (pinfunction "VSS_31") (pintype "power_in"))
      (node (ref "U2") (pin "51") (pinfunction "VSS_51") (pintype "power_in"))
      (node (ref "U2") (pin "70") (pinfunction "VSS_70") (pintype "power_in"))
      (node (ref "U2") (pin "79") (pinfunction "CSDI/RG12_79") (pintype "bidirectional"))
      (node (ref "U3") (pin "2") (pinfunction "GND_2") (pintype "power_in"))
      (node (ref "U4") (pin "10") (pinfunction "VSS_10") (pintype "power_in"))
      (node (ref "U5") (pin "8") (pinfunction "GND_8") (pintype "passive"))
      (node (ref "U6") (pin "4") (pinfunction "GND_4") (pintype "power_in"))
      (node (ref "U6") (pin "8") (pinfunction "GND_8") (pintype "power_in"))
      (node (ref "U7") (pin "2") (pinfunction "GND_2") (pintype "power_in"))
      (node (ref "U8") (pin "10") (pinfunction "VSS_10") (pintype "power_in"))
      (node (ref "U9") (pin "10") (pinfunction "VSS_10") (pintype "power_in"))
    )
    (net (code "36") (name "Net-(C15-Pad2)") (class "Default")
      (node (ref "C15") (pin "2") (pinfunction "2_2") (pintype "passive"))
      (node (ref "R11") (pin "2") (pinfunction "2_2") (pintype "passive"))
      (node (ref "R12") (pin "1") (pinfunction "1_1") (pintype "passive"))
    )
    (net (code "37") (name "Net-(C24-Pad1)") (class "Default")
      (node (ref "C24") (pin "1") (pinfunction "1_1") (pintype "passive"))
      (node (ref "C25") (pin "1") (pinfunction "1_1") (pintype "passive"))
      (node (ref "R12") (pin "2") (pinfunction "2_2") (pintype "passive"))
    )
    (net (code "38") (name "Net-(C25-Pad2)") (class "Default")
      (node (ref "C25") (pin "2") (pinfunction "2_2") (pintype "passive"))
      (node (ref "R13") (pin "1") (pinfunction "1_1") (pintype "passive"))
    )
    (net (code "39") (name "Net-(D2-K)") (class "Default")
      (node (ref "C12") (pin "2") (pinfunction "2_2") (pintype "passive"))
      (node (ref "D2") (pin "2") (pinfunction "K_2") (pintype "passive"))
      (node (ref "L1") (pin "1") (pinfunction "1_1") (pintype "passive"))
      (node (ref "U6") (pin "1") (pinfunction "OUT_1") (pintype "power_in"))
    )
    (net (code "40") (name "Net-(D3-K)") (class "Default")
      (node (ref "D3") (pin "3") (pinfunction "K_3") (pintype "passive"))
      (node (ref "J13") (pin "1") (pinfunction "VBUS_1") (pintype "power_in"))
      (node (ref "U14") (pin "8") (pinfunction "VBUS_8") (pintype "input"))
    )
    (net (code "41") (name "Net-(D4-K)") (class "Default")
      (node (ref "D4") (pin "3") (pinfunction "K_3") (pintype "passive"))
      (node (ref "J13") (pin "2") (pinfunction "D-_2") (pintype "input"))
      (node (ref "U14") (pin "5") (pinfunction "D-_5") (pintype "bidirectional"))
    )
    (net (code "42") (name "Net-(D5-K)") (class "Default")
      (node (ref "D5") (pin "3") (pinfunction "K_3") (pintype "passive"))
      (node (ref "J13") (pin "3") (pinfunction "D+_3") (pintype "input"))
      (node (ref "U14") (pin "4") (pinfunction "D+_4") (pintype "bidirectional"))
    )
    (net (code "43") (name "Net-(D7-K)") (class "Default")
      (node (ref "C26") (pin "2") (pinfunction "2_2") (pintype "passive"))
      (node (ref "D7") (pin "2") (pinfunction "K_2") (pintype "passive"))
      (node (ref "L2") (pin "1") (pinfunction "1_1") (pintype "passive"))
      (node (ref "U11") (pin "1") (pinfunction "OUT_1") (pintype "power_in"))
    )
    (net (code "44") (name "Net-(DS1-K-Pad1)") (class "Default")
      (node (ref "DS1") (pin "1") (pinfunction "K_1") (pintype "passive"))
      (node (ref "DS1") (pin "3") (pinfunction "K_3") (pintype "passive"))
      (node (ref "DS1") (pin "4") (pinfunction "K_4") (pintype "passive"))
      (node (ref "R46") (pin "2") (pinfunction "2_2") (pintype "passive"))
    )
    (net (code "45") (name "Net-(DS2-K-Pad1)") (class "Default")
      (node (ref "DS2") (pin "1") (pinfunction "K_1") (pintype "passive"))
      (node (ref "DS2") (pin "3") (pinfunction "K_3") (pintype "passive"))
      (node (ref "DS2") (pin "4") (pinfunction "K_4") (pintype "passive"))
      (node (ref "R47") (pin "2") (pinfunction "2_2") (pintype "passive"))
    )
    (net (code "46") (name "Net-(DS3-K-Pad1)") (class "Default")
      (node (ref "DS3") (pin "1") (pinfunction "K_1") (pintype "passive"))
      (node (ref "DS3") (pin "3") (pinfunction "K_3") (pintype "passive"))
      (node (ref "DS3") (pin "4") (pinfunction "K_4") (pintype "passive"))
      (node (ref "R58") (pin "2") (pinfunction "2_2") (pintype "passive"))
    )
    (net (code "47") (name "Net-(DS4-K-Pad1)") (class "Default")
      (node (ref "DS4") (pin "1") (pinfunction "K_1") (pintype "passive"))
      (node (ref "DS4") (pin "3") (pinfunction "K_3") (pintype "passive"))
      (node (ref "DS4") (pin "4") (pinfunction "K_4") (pintype "passive"))
      (node (ref "R59") (pin "2") (pinfunction "2_2") (pintype "passive"))
    )
    (net (code "48") (name "Net-(DS5-K-Pad1)") (class "Default")
      (node (ref "DS5") (pin "1") (pinfunction "K_1") (pintype "passive"))
      (node (ref "DS5") (pin "3") (pinfunction "K_3") (pintype "passive"))
      (node (ref "DS5") (pin "4") (pinfunction "K_4") (pintype "passive"))
      (node (ref "R48") (pin "2") (pinfunction "2_2") (pintype "passive"))
    )
    (net (code "49") (name "Net-(DS6-K-Pad1)") (class "Default")
      (node (ref "DS6") (pin "1") (pinfunction "K_1") (pintype "passive"))
      (node (ref "DS6") (pin "3") (pinfunction "K_3") (pintype "passive"))
      (node (ref "DS6") (pin "4") (pinfunction "K_4") (pintype "passive"))
      (node (ref "R49") (pin "2") (pinfunction "2_2") (pintype "passive"))
    )
    (net (code "50") (name "Net-(DS7-K-Pad1)") (class "Default")
      (node (ref "DS7") (pin "1") (pinfunction "K_1") (pintype "passive"))
      (node (ref "DS7") (pin "3") (pinfunction "K_3") (pintype "passive"))
      (node (ref "DS7") (pin "4") (pinfunction "K_4") (pintype "passive"))
      (node (ref "R60") (pin "2") (pinfunction "2_2") (pintype "passive"))
    )
    (net (code "51") (name "Net-(DS8-K-Pad1)") (class "Default")
      (node (ref "DS8") (pin "1") (pinfunction "K_1") (pintype "passive"))
      (node (ref "DS8") (pin "3") (pinfunction "K_3") (pintype "passive"))
      (node (ref "DS8") (pin "4") (pinfunction "K_4") (pintype "passive"))
      (node (ref "R61") (pin "2") (pinfunction "2_2") (pintype "passive"))
    )
    (net (code "52") (name "Net-(DS9-K-Pad1)") (class "Default")
      (node (ref "DS9") (pin "1") (pinfunction "K_1") (pintype "passive"))
      (node (ref "DS9") (pin "3") (pinfunction "K_3") (pintype "passive"))
      (node (ref "DS9") (pin "4") (pinfunction "K_4") (pintype "passive"))
      (node (ref "R50") (pin "2") (pinfunction "2_2") (pintype "passive"))
    )
    (net (code "53") (name "Net-(DS10-K-Pad1)") (class "Default")
      (node (ref "DS10") (pin "1") (pinfunction "K_1") (pintype "passive"))
      (node (ref "DS10") (pin "3") (pinfunction "K_3") (pintype "passive"))
      (node (ref "DS10") (pin "4") (pinfunction "K_4") (pintype "passive"))
      (node (ref "R51") (pin "2") (pinfunction "2_2") (pintype "passive"))
    )
    (net (code "54") (name "Net-(DS11-K-Pad1)") (class "Default")
      (node (ref "DS11") (pin "1") (pinfunction "K_1") (pintype "passive"))
      (node (ref "DS11") (pin "3") (pinfunction "K_3") (pintype "passive"))
      (node (ref "DS11") (pin "4") (pinfunction "K_4") (pintype "passive"))
      (node (ref "R62") (pin "2") (pinfunction "2_2") (pintype "passive"))
    )
    (net (code "55") (name "Net-(DS12-K-Pad1)") (class "Default")
      (node (ref "DS12") (pin "1") (pinfunction "K_1") (pintype "passive"))
      (node (ref "DS12") (pin "3") (pinfunction "K_3") (pintype "passive"))
      (node (ref "DS12") (pin "4") (pinfunction "K_4") (pintype "passive"))
      (node (ref "R63") (pin "2") (pinfunction "2_2") (pintype "passive"))
    )
    (net (code "56") (name "Net-(DS13-K-Pad1)") (class "Default")
      (node (ref "DS13") (pin "1") (pinfunction "K_1") (pintype "passive"))
      (node (ref "DS13") (pin "3") (pinfunction "K_3") (pintype "passive"))
      (node (ref "DS13") (pin "4") (pinfunction "K_4") (pintype "passive"))
      (node (ref "R52") (pin "2") (pinfunction "2_2") (pintype "passive"))
    )
    (net (code "57") (name "Net-(DS14-K-Pad1)") (class "Default")
      (node (ref "DS14") (pin "1") (pinfunction "K_1") (pintype "passive"))
      (node (ref "DS14") (pin "3") (pinfunction "K_3") (pintype "passive"))
      (node (ref "DS14") (pin "4") (pinfunction "K_4") (pintype "passive"))
      (node (ref "R53") (pin "2") (pinfunction "2_2") (pintype "passive"))
    )
    (net (code "58") (name "Net-(DS15-K-Pad1)") (class "Default")
      (node (ref "DS15") (pin "1") (pinfunction "K_1") (pintype "passive"))
      (node (ref "DS15") (pin "3") (pinfunction "K_3") (pintype "passive"))
      (node (ref "DS15") (pin "4") (pinfunction "K_4") (pintype "passive"))
      (node (ref "R64") (pin "2") (pinfunction "2_2") (pintype "passive"))
    )
    (net (code "59") (name "Net-(DS16-K-Pad1)") (class "Default")
      (node (ref "DS16") (pin "1") (pinfunction "K_1") (pintype "passive"))
      (node (ref "DS16") (pin "3") (pinfunction "K_3") (pintype "passive"))
      (node (ref "DS16") (pin "4") (pinfunction "K_4") (pintype "passive"))
      (node (ref "R65") (pin "2") (pinfunction "2_2") (pintype "passive"))
    )
    (net (code "60") (name "Net-(DS17-K-Pad1)") (class "Default")
      (node (ref "DS17") (pin "1") (pinfunction "K_1") (pintype "passive"))
      (node (ref "DS17") (pin "3") (pinfunction "K_3") (pintype "passive"))
      (node (ref "DS17") (pin "4") (pinfunction "K_4") (pintype "passive"))
      (node (ref "R54") (pin "2") (pinfunction "2_2") (pintype "passive"))
    )
    (net (code "61") (name "Net-(DS18-K-Pad1)") (class "Default")
      (node (ref "DS18") (pin "1") (pinfunction "K_1") (pintype "passive"))
      (node (ref "DS18") (pin "3") (pinfunction "K_3") (pintype "passive"))
      (node (ref "DS18") (pin "4") (pinfunction "K_4") (pintype "passive"))
      (node (ref "R55") (pin "2") (pinfunction "2_2") (pintype "passive"))
    )
    (net (code "62") (name "Net-(DS19-K-Pad1)") (class "Default")
      (node (ref "DS19") (pin "1") (pinfunction "K_1") (pintype "passive"))
      (node (ref "DS19") (pin "3") (pinfunction "K_3") (pintype "passive"))
      (node (ref "DS19") (pin "4") (pinfunction "K_4") (pintype "passive"))
      (node (ref "R66") (pin "2") (pinfunction "2_2") (pintype "passive"))
    )
    (net (code "63") (name "Net-(DS20-K-Pad1)") (class "Default")
      (node (ref "DS20") (pin "1") (pinfunction "K_1") (pintype "passive"))
      (node (ref "DS20") (pin "3") (pinfunction "K_3") (pintype "passive"))
      (node (ref "DS20") (pin "4") (pinfunction "K_4") (pintype "passive"))
      (node (ref "R67") (pin "2") (pinfunction "2_2") (pintype "passive"))
    )
    (net (code "64") (name "Net-(DS21-K-Pad1)") (class "Default")
      (node (ref "DS21") (pin "1") (pinfunction "K_1") (pintype "passive"))
      (node (ref "DS21") (pin "3") (pinfunction "K_3") (pintype "passive"))
      (node (ref "DS21") (pin "4") (pinfunction "K_4") (pintype "passive"))
      (node (ref "R56") (pin "2") (pinfunction "2_2") (pintype "passive"))
    )
    (net (code "65") (name "Net-(DS22-K-Pad1)") (class "Default")
      (node (ref "DS22") (pin "1") (pinfunction "K_1") (pintype "passive"))
      (node (ref "DS22") (pin "3") (pinfunction "K_3") (pintype "passive"))
      (node (ref "DS22") (pin "4") (pinfunction "K_4") (pintype "passive"))
      (node (ref "R57") (pin "2") (pinfunction "2_2") (pintype "passive"))
    )
    (net (code "66") (name "Net-(DS23-K-Pad1)") (class "Default")
      (node (ref "DS23") (pin "1") (pinfunction "K_1") (pintype "passive"))
      (node (ref "DS23") (pin "3") (pinfunction "K_3") (pintype "passive"))
      (node (ref "DS23") (pin "4") (pinfunction "K_4") (pintype "passive"))
      (node (ref "R68") (pin "2") (pinfunction "2_2") (pintype "passive"))
    )
    (net (code "67") (name "Net-(DS24-K-Pad1)") (class "Default")
      (node (ref "DS24") (pin "1") (pinfunction "K_1") (pintype "passive"))
      (node (ref "DS24") (pin "3") (pinfunction "K_3") (pintype "passive"))
      (node (ref "DS24") (pin "4") (pinfunction "K_4") (pintype "passive"))
      (node (ref "R69") (pin "2") (pinfunction "2_2") (pintype "passive"))
    )
    (net (code "68") (name "Net-(DS25-K-Pad1)") (class "Default")
      (node (ref "DS25") (pin "1") (pinfunction "K_1") (pintype "passive"))
      (node (ref "DS25") (pin "3") (pinfunction "K_3") (pintype "passive"))
      (node (ref "DS25") (pin "4") (pinfunction "K_4") (pintype "passive"))
      (node (ref "R88") (pin "2") (pinfunction "2_2") (pintype "passive"))
    )
    (net (code "69") (name "Net-(DS26-K-Pad1)") (class "Default")
      (node (ref "DS26") (pin "1") (pinfunction "K_1") (pintype "passive"))
      (node (ref "DS26") (pin "3") (pinfunction "K_3") (pintype "passive"))
      (node (ref "DS26") (pin "4") (pinfunction "K_4") (pintype "passive"))
      (node (ref "R89") (pin "2") (pinfunction "2_2") (pintype "passive"))
    )
    (net (code "70") (name "Net-(DS27-K-Pad1)") (class "Default")
      (node (ref "DS27") (pin "1") (pinfunction "K_1") (pintype "passive"))
      (node (ref "DS27") (pin "3") (pinfunction "K_3") (pintype "passive"))
      (node (ref "DS27") (pin "4") (pinfunction "K_4") (pintype "passive"))
      (node (ref "R100") (pin "2") (pinfunction "2_2") (pintype "passive"))
    )
    (net (code "71") (name "Net-(DS28-K-Pad1)") (class "Default")
      (node (ref "DS28") (pin "1") (pinfunction "K_1") (pintype "passive"))
      (node (ref "DS28") (pin "3") (pinfunction "K_3") (pintype "passive"))
      (node (ref "DS28") (pin "4") (pinfunction "K_4") (pintype "passive"))
      (node (ref "R101") (pin "2") (pinfunction "2_2") (pintype "passive"))
    )
    (net (code "72") (name "Net-(DS29-K-Pad1)") (class "Default")
      (node (ref "DS29") (pin "1") (pinfunction "K_1") (pintype "passive"))
      (node (ref "DS29") (pin "3") (pinfunction "K_3") (pintype "passive"))
      (node (ref "DS29") (pin "4") (pinfunction "K_4") (pintype "passive"))
      (node (ref "R90") (pin "2") (pinfunction "2_2") (pintype "passive"))
    )
    (net (code "73") (name "Net-(DS30-K-Pad1)") (class "Default")
      (node (ref "DS30") (pin "1") (pinfunction "K_1") (pintype "passive"))
      (node (ref "DS30") (pin "3") (pinfunction "K_3") (pintype "passive"))
      (node (ref "DS30") (pin "4") (pinfunction "K_4") (pintype "passive"))
      (node (ref "R91") (pin "2") (pinfunction "2_2") (pintype "passive"))
    )
    (net (code "74") (name "Net-(DS31-K-Pad1)") (class "Default")
      (node (ref "DS31") (pin "1") (pinfunction "K_1") (pintype "passive"))
      (node (ref "DS31") (pin "3") (pinfunction "K_3") (pintype "passive"))
      (node (ref "DS31") (pin "4") (pinfunction "K_4") (pintype "passive"))
      (node (ref "R102") (pin "2") (pinfunction "2_2") (pintype "passive"))
    )
    (net (code "75") (name "Net-(DS32-K-Pad1)") (class "Default")
      (node (ref "DS32") (pin "1") (pinfunction "K_1") (pintype "passive"))
      (node (ref "DS32") (pin "3") (pinfunction "K_3") (pintype "passive"))
      (node (ref "DS32") (pin "4") (pinfunction "K_4") (pintype "passive"))
      (node (ref "R103") (pin "2") (pinfunction "2_2") (pintype "passive"))
    )
    (net (code "76") (name "Net-(DS33-K-Pad1)") (class "Default")
      (node (ref "DS33") (pin "1") (pinfunction "K_1") (pintype "passive"))
      (node (ref "DS33") (pin "3") (pinfunction "K_3") (pintype "passive"))
      (node (ref "DS33") (pin "4") (pinfunction "K_4") (pintype "passive"))
      (node (ref "R92") (pin "2") (pinfunction "2_2") (pintype "passive"))
    )
    (net (code "77") (name "Net-(DS34-K-Pad1)") (class "Default")
      (node (ref "DS34") (pin "1") (pinfunction "K_1") (pintype "passive"))
      (node (ref "DS34") (pin "3") (pinfunction "K_3") (pintype "passive"))
      (node (ref "DS34") (pin "4") (pinfunction "K_4") (pintype "passive"))
      (node (ref "R93") (pin "2") (pinfunction "2_2") (pintype "passive"))
    )
    (net (code "78") (name "Net-(DS35-K-Pad1)") (class "Default")
      (node (ref "DS35") (pin "1") (pinfunction "K_1") (pintype "passive"))
      (node (ref "DS35") (pin "3") (pinfunction "K_3") (pintype "passive"))
      (node (ref "DS35") (pin "4") (pinfunction "K_4") (pintype "passive"))
      (node (ref "R104") (pin "2") (pinfunction "2_2") (pintype "passive"))
    )
    (net (code "79") (name "Net-(DS36-K-Pad1)") (class "Default")
      (node (ref "DS36") (pin "1") (pinfunction "K_1") (pintype "passive"))
      (node (ref "DS36") (pin "3") (pinfunction "K_3") (pintype "passive"))
      (node (ref "DS36") (pin "4") (pinfunction "K_4") (pintype "passive"))
      (node (ref "R105") (pin "2") (pinfunction "2_2") (pintype "passive"))
    )
    (net (code "80") (name "Net-(DS37-K-Pad1)") (class "Default")
      (node (ref "DS37") (pin "1") (pinfunction "K_1") (pintype "passive"))
      (node (ref "DS37") (pin "3") (pinfunction "K_3") (pintype "passive"))
      (node (ref "DS37") (pin "4") (pinfunction "K_4") (pintype "passive"))
      (node (ref "R94") (pin "2") (pinfunction "2_2") (pintype "passive"))
    )
    (net (code "81") (name "Net-(DS38-K-Pad1)") (class "Default")
      (node (ref "DS38") (pin "1") (pinfunction "K_1") (pintype "passive"))
      (node (ref "DS38") (pin "3") (pinfunction "K_3") (pintype "passive"))
      (node (ref "DS38") (pin "4") (pinfunction "K_4") (pintype "passive"))
      (node (ref "R95") (pin "2") (pinfunction "2_2") (pintype "passive"))
    )
    (net (code "82") (name "Net-(DS39-K-Pad1)") (class "Default")
      (node (ref "DS39") (pin "1") (pinfunction "K_1") (pintype "passive"))
      (node (ref "DS39") (pin "3") (pinfunction "K_3") (pintype "passive"))
      (node (ref "DS39") (pin "4") (pinfunction "K_4") (pintype "passive"))
      (node (ref "R106") (pin "2") (pinfunction "2_2") (pintype "passive"))
    )
    (net (code "83") (name "Net-(DS40-K-Pad1)") (class "Default")
      (node (ref "DS40") (pin "1") (pinfunction "K_1") (pintype "passive"))
      (node (ref "DS40") (pin "3") (pinfunction "K_3") (pintype "passive"))
      (node (ref "DS40") (pin "4") (pinfunction "K_4") (pintype "passive"))
      (node (ref "R107") (pin "2") (pinfunction "2_2") (pintype "passive"))
    )
    (net (code "84") (name "Net-(DS41-K-Pad1)") (class "Default")
      (node (ref "DS41") (pin "1") (pinfunction "K_1") (pintype "passive"))
      (node (ref "DS41") (pin "3") (pinfunction "K_3") (pintype "passive"))
      (node (ref "DS41") (pin "4") (pinfunction "K_4") (pintype "passive"))
      (node (ref "R96") (pin "2") (pinfunction "2_2") (pintype "passive"))
    )
    (net (code "85") (name "Net-(DS42-K-Pad1)") (class "Default")
      (node (ref "DS42") (pin "1") (pinfunction "K_1") (pintype "passive"))
      (node (ref "DS42") (pin "3") (pinfunction "K_3") (pintype "passive"))
      (node (ref "DS42") (pin "4") (pinfunction "K_4") (pintype "passive"))
      (node (ref "R97") (pin "2") (pinfunction "2_2") (pintype "passive"))
    )
    (net (code "86") (name "Net-(DS43-K-Pad1)") (class "Default")
      (node (ref "DS43") (pin "1") (pinfunction "K_1") (pintype "passive"))
      (node (ref "DS43") (pin "3") (pinfunction "K_3") (pintype "passive"))
      (node (ref "DS43") (pin "4") (pinfunction "K_4") (pintype "passive"))
      (node (ref "R108") (pin "2") (pinfunction "2_2") (pintype "passive"))
    )
    (net (code "87") (name "Net-(DS44-K-Pad1)") (class "Default")
      (node (ref "DS44") (pin "1") (pinfunction "K_1") (pintype "passive"))
      (node (ref "DS44") (pin "3") (pinfunction "K_3") (pintype "passive"))
      (node (ref "DS44") (pin "4") (pinfunction "K_4") (pintype "passive"))
      (node (ref "R109") (pin "2") (pinfunction "2_2") (pintype "passive"))
    )
    (net (code "88") (name "Net-(DS45-K-Pad1)") (class "Default")
      (node (ref "DS45") (pin "1") (pinfunction "K_1") (pintype "passive"))
      (node (ref "DS45") (pin "3") (pinfunction "K_3") (pintype "passive"))
      (node (ref "DS45") (pin "4") (pinfunction "K_4") (pintype "passive"))
      (node (ref "R98") (pin "2") (pinfunction "2_2") (pintype "passive"))
    )
    (net (code "89") (name "Net-(DS46-K-Pad1)") (class "Default")
      (node (ref "DS46") (pin "1") (pinfunction "K_1") (pintype "passive"))
      (node (ref "DS46") (pin "3") (pinfunction "K_3") (pintype "passive"))
      (node (ref "DS46") (pin "4") (pinfunction "K_4") (pintype "passive"))
      (node (ref "R99") (pin "2") (pinfunction "2_2") (pintype "passive"))
    )
    (net (code "90") (name "Net-(DS47-K-Pad1)") (class "Default")
      (node (ref "DS47") (pin "1") (pinfunction "K_1") (pintype "passive"))
      (node (ref "DS47") (pin "3") (pinfunction "K_3") (pintype "passive"))
      (node (ref "DS47") (pin "4") (pinfunction "K_4") (pintype "passive"))
      (node (ref "R110") (pin "2") (pinfunction "2_2") (pintype "passive"))
    )
    (net (code "91") (name "Net-(DS48-K-Pad1)") (class "Default")
      (node (ref "DS48") (pin "1") (pinfunction "K_1") (pintype "passive"))
      (node (ref "DS48") (pin "3") (pinfunction "K_3") (pintype "passive"))
      (node (ref "DS48") (pin "4") (pinfunction "K_4") (pintype "passive"))
      (node (ref "R111") (pin "2") (pinfunction "2_2") (pintype "passive"))
    )
    (net (code "92") (name "Net-(DS49-A)") (class "Default")
      (node (ref "DS49") (pin "1") (pinfunction "A_1") (pintype "passive"))
      (node (ref "Q1") (pin "4") (pinfunction "G_4") (pintype "passive"))
      (node (ref "R28") (pin "2") (pinfunction "2_2") (pintype "passive"))
    )
    (net (code "93") (name "Net-(DS50-A)") (class "Default")
      (node (ref "DS50") (pin "1") (pinfunction "A_1") (pintype "passive"))
      (node (ref "Q2") (pin "4") (pinfunction "G_4") (pintype "passive"))
      (node (ref "R40") (pin "2") (pinfunction "2_2") (pintype "passive"))
    )
    (net (code "94") (name "Net-(J2-.125_AMP-IN)") (class "Default")
      (node (ref "D1") (pin "A") (pinfunction "A_A") (pintype "passive"))
      (node (ref "J2") (pin "1") (pinfunction ".125_AMP-IN_1") (pintype "passive"))
      (node (ref "J6") (pin "1") (pinfunction ".125_AMP-IN_1") (pintype "passive"))
    )
    (net (code "95") (name "Net-(J3-.125_AMP-IN)") (class "Default")
      (node (ref "J3") (pin "1") (pinfunction ".125_AMP-IN_1") (pintype "passive"))
      (node (ref "J7") (pin "1") (pinfunction ".125_AMP-IN_1") (pintype "passive"))
      (node (ref "R5") (pin "2") (pinfunction "2_2") (pintype "passive"))
      (node (ref "U3") (pin "7") (pinfunction "CANH_7") (pintype "bidirectional"))
    )
    (net (code "96") (name "Net-(J4-.125_AMP-IN)") (class "Default")
      (node (ref "J4") (pin "1") (pinfunction ".125_AMP-IN_1") (pintype "passive"))
      (node (ref "J8") (pin "1") (pinfunction ".125_AMP-IN_1") (pintype "passive"))
      (node (ref "R5") (pin "1") (pinfunction "1_1") (pintype "passive"))
      (node (ref "U3") (pin "6") (pinfunction "CANL_6") (pintype "bidirectional"))
    )
    (net (code "97") (name "Net-(J9-.125_AMP-IN)") (class "Default")
      (node (ref "J9") (pin "1") (pinfunction ".125_AMP-IN_1") (pintype "passive"))
      (node (ref "R16") (pin "2") (pinfunction "2_2") (pintype "passive"))
      (node (ref "U10") (pin "5") (pinfunction "VOUT1_5") (pintype "output"))
    )
    (net (code "98") (name "Net-(J10-.125_AMP-IN)") (class "Default")
      (node (ref "J10") (pin "1") (pinfunction ".125_AMP-IN_1") (pintype "passive"))
      (node (ref "U10") (pin "8") (pinfunction "VOUT2_8") (pintype "output"))
    )
    (net (code "99") (name "Net-(J11-.125_AMP-IN)") (class "Default")
      (node (ref "J11") (pin "1") (pinfunction ".125_AMP-IN_1") (pintype "passive"))
      (node (ref "R128") (pin "1") (pinfunction "1_1") (pintype "passive"))
    )
    (net (code "100") (name "Net-(Q1-D-Pad5)") (class "Default")
      (node (ref "Q1") (pin "5") (pinfunction "D_5") (pintype "passive"))
      (node (ref "Q1") (pin "6") (pinfunction "D_6") (pintype "passive"))
      (node (ref "Q1") (pin "7") (pinfunction "D_7") (pintype "passive"))
      (node (ref "Q1") (pin "8") (pinfunction "D_8") (pintype "passive"))
      (node (ref "R46") (pin "1") (pinfunction "1_1") (pintype "passive"))
      (node (ref "R47") (pin "1") (pinfunction "1_1") (pintype "passive"))
      (node (ref "R48") (pin "1") (pinfunction "1_1") (pintype "passive"))
      (node (ref "R49") (pin "1") (pinfunction "1_1") (pintype "passive"))
      (node (ref "R50") (pin "1") (pinfunction "1_1") (pintype "passive"))
      (node (ref "R51") (pin "1") (pinfunction "1_1") (pintype "passive"))
      (node (ref "R52") (pin "1") (pinfunction "1_1") (pintype "passive"))
      (node (ref "R53") (pin "1") (pinfunction "1_1") (pintype "passive"))
      (node (ref "R54") (pin "1") (pinfunction "1_1") (pintype "passive"))
      (node (ref "R55") (pin "1") (pinfunction "1_1") (pintype "passive"))
      (node (ref "R56") (pin "1") (pinfunction "1_1") (pintype "passive"))
      (node (ref "R57") (pin "1") (pinfunction "1_1") (pintype "passive"))
      (node (ref "R88") (pin "1") (pinfunction "1_1") (pintype "passive"))
      (node (ref "R89") (pin "1") (pinfunction "1_1") (pintype "passive"))
      (node (ref "R90") (pin "1") (pinfunction "1_1") (pintype "passive"))
      (node (ref "R91") (pin "1") (pinfunction "1_1") (pintype "passive"))
      (node (ref "R92") (pin "1") (pinfunction "1_1") (pintype "passive"))
      (node (ref "R93") (pin "1") (pinfunction "1_1") (pintype "passive"))
      (node (ref "R94") (pin "1") (pinfunction "1_1") (pintype "passive"))
      (node (ref "R95") (pin "1") (pinfunction "1_1") (pintype "passive"))
      (node (ref "R96") (pin "1") (pinfunction "1_1") (pintype "passive"))
      (node (ref "R97") (pin "1") (pinfunction "1_1") (pintype "passive"))
      (node (ref "R98") (pin "1") (pinfunction "1_1") (pintype "passive"))
      (node (ref "R99") (pin "1") (pinfunction "1_1") (pintype "passive"))
    )
    (net (code "101") (name "Net-(Q2-D-Pad5)") (class "Default")
      (node (ref "Q2") (pin "5") (pinfunction "D_5") (pintype "passive"))
      (node (ref "Q2") (pin "6") (pinfunction "D_6") (pintype "passive"))
      (node (ref "Q2") (pin "7") (pinfunction "D_7") (pintype "passive"))
      (node (ref "Q2") (pin "8") (pinfunction "D_8") (pintype "passive"))
      (node (ref "R100") (pin "1") (pinfunction "1_1") (pintype "passive"))
      (node (ref "R101") (pin "1") (pinfunction "1_1") (pintype "passive"))
      (node (ref "R102") (pin "1") (pinfunction "1_1") (pintype "passive"))
      (node (ref "R103") (pin "1") (pinfunction "1_1") (pintype "passive"))
      (node (ref "R104") (pin "1") (pinfunction "1_1") (pintype "passive"))
      (node (ref "R105") (pin "1") (pinfunction "1_1") (pintype "passive"))
      (node (ref "R106") (pin "1") (pinfunction "1_1") (pintype "passive"))
      (node (ref "R107") (pin "1") (pinfunction "1_1") (pintype "passive"))
      (node (ref "R108") (pin "1") (pinfunction "1_1") (pintype "passive"))
      (node (ref "R109") (pin "1") (pinfunction "1_1") (pintype "passive"))
      (node (ref "R110") (pin "1") (pinfunction "1_1") (pintype "passive"))
      (node (ref "R111") (pin "1") (pinfunction "1_1") (pintype "passive"))
      (node (ref "R58") (pin "1") (pinfunction "1_1") (pintype "passive"))
      (node (ref "R59") (pin "1") (pinfunction "1_1") (pintype "passive"))
      (node (ref "R60") (pin "1") (pinfunction "1_1") (pintype "passive"))
      (node (ref "R61") (pin "1") (pinfunction "1_1") (pintype "passive"))
      (node (ref "R62") (pin "1") (pinfunction "1_1") (pintype "passive"))
      (node (ref "R63") (pin "1") (pinfunction "1_1") (pintype "passive"))
      (node (ref "R64") (pin "1") (pinfunction "1_1") (pintype "passive"))
      (node (ref "R65") (pin "1") (pinfunction "1_1") (pintype "passive"))
      (node (ref "R66") (pin "1") (pinfunction "1_1") (pintype "passive"))
      (node (ref "R67") (pin "1") (pinfunction "1_1") (pintype "passive"))
      (node (ref "R68") (pin "1") (pinfunction "1_1") (pintype "passive"))
      (node (ref "R69") (pin "1") (pinfunction "1_1") (pintype "passive"))
    )
    (net (code "102") (name "Net-(R128-Pad2)") (class "Default")
      (node (ref "R128") (pin "2") (pinfunction "2_2") (pintype "passive"))
      (node (ref "R22") (pin "1") (pinfunction "1_1") (pintype "passive"))
      (node (ref "U12") (pin "2") (pinfunction "2_2") (pintype "passive"))
      (node (ref "U12") (pin "3") (pinfunction "3_3") (pintype "passive"))
    )
    (net (code "103") (name "Net-(U1-~{HOLD})") (class "Default")
      (node (ref "R2") (pin "2") (pinfunction "2_2") (pintype "passive"))
      (node (ref "U1") (pin "1") (pinfunction "~{HOLD}_1") (pintype "input"))
      (node (ref "U4") (pin "1") (pinfunction "~{HOLD}_1") (pintype "input"))
      (node (ref "U8") (pin "1") (pinfunction "~{HOLD}_1") (pintype "input"))
      (node (ref "U9") (pin "1") (pinfunction "~{HOLD}_1") (pintype "input"))
    )
    (net (code "104") (name "Net-(U2-OSC1{slash}CLKIN)") (class "Default")
      (node (ref "C20") (pin "1") (pinfunction "1_1") (pintype "passive"))
      (node (ref "U2") (pin "49") (pinfunction "OSC1/CLKIN_49") (pintype "input"))
      (node (ref "Y1") (pin "1") (pinfunction "OSC1_1") (pintype "passive"))
    )
    (net (code "105") (name "Net-(U5-AOUTR)") (class "Default")
      (node (ref "C15") (pin "1") (pinfunction "1_1") (pintype "passive"))
      (node (ref "U5") (pin "10") (pinfunction "AOUTR_10") (pintype "passive"))
    )
    (net (code "106") (name "Net-(U5-FILT+)") (class "Default")
      (node (ref "C14") (pin "1") (pinfunction "1_1") (pintype "passive"))
      (node (ref "U5") (pin "6") (pinfunction "FILT+_6") (pintype "passive"))
    )
    (net (code "107") (name "Net-(U5-VQ)") (class "Default")
      (node (ref "C6") (pin "1") (pinfunction "1_1") (pintype "passive"))
      (node (ref "C9") (pin "1") (pinfunction "1_1") (pintype "passive"))
      (node (ref "U5") (pin "5") (pinfunction "VQ_5") (pintype "passive"))
    )
    (net (code "108") (name "Net-(U6-CBOOST)") (class "Default")
      (node (ref "C12") (pin "1") (pinfunction "1_1") (pintype "passive"))
      (node (ref "U6") (pin "3") (pinfunction "CBOOST_3") (pintype "power_in"))
    )
    (net (code "109") (name "Net-(U6-FB)") (class "Default")
      (node (ref "R7") (pin "2") (pinfunction "2_2") (pintype "passive"))
      (node (ref "R9") (pin "1") (pinfunction "1_1") (pintype "passive"))
      (node (ref "U6") (pin "6") (pinfunction "FB_6") (pintype "input"))
    )
    (net (code "110") (name "Net-(U6-~{ON}{slash}OFF)") (class "Default")
      (node (ref "R130") (pin "2") (pinfunction "2_2") (pintype "passive"))
      (node (ref "U6") (pin "7") (pinfunction "~{ON}/OFF_7") (pintype "input"))
    )
    (net (code "111") (name "Net-(U10-BYP)") (class "Default")
      (node (ref "C28") (pin "1") (pinfunction "1_1") (pintype "passive"))
      (node (ref "U10") (pin "2") (pinfunction "BYP_2") (pintype "passive"))
      (node (ref "U10") (pin "3") (pinfunction "IN+_3") (pintype "input"))
    )
    (net (code "112") (name "Net-(U10-IN-)") (class "Default")
      (node (ref "R13") (pin "2") (pinfunction "2_2") (pintype "passive"))
      (node (ref "R16") (pin "1") (pinfunction "1_1") (pintype "passive"))
      (node (ref "U10") (pin "4") (pinfunction "IN-_4") (pintype "input"))
    )
    (net (code "113") (name "Net-(U11-CBOOST)") (class "Default")
      (node (ref "C26") (pin "1") (pinfunction "1_1") (pintype "passive"))
      (node (ref "U11") (pin "3") (pinfunction "CBOOST_3") (pintype "power_in"))
    )
    (net (code "114") (name "Net-(U11-FB)") (class "Default")
      (node (ref "R17") (pin "2") (pinfunction "2_2") (pintype "passive"))
      (node (ref "R18") (pin "1") (pinfunction "1_1") (pintype "passive"))
      (node (ref "U11") (pin "6") (pinfunction "FB_6") (pintype "input"))
    )
    (net (code "115") (name "Net-(U11-~{ON}{slash}OFF)") (class "Default")
      (node (ref "R20") (pin "2") (pinfunction "2_2") (pintype "passive"))
      (node (ref "U11") (pin "7") (pinfunction "~{ON}/OFF_7") (pintype "input"))
    )
    (net (code "116") (name "Net-(U13-A)") (class "Default")
      (node (ref "R29") (pin "1") (pinfunction "1_1") (pintype "passive"))
      (node (ref "R8") (pin "1") (pinfunction "1_1") (pintype "passive"))
      (node (ref "U13") (pin "2") (pinfunction "A_2") (pintype "input"))
      (node (ref "U2") (pin "50") (pinfunction "OSC2/CLK0/RC15_50") (pintype "bidirectional"))
    )
    (net (code "117") (name "Net-(Y1-OSC2)") (class "Default")
      (node (ref "C16") (pin "1") (pinfunction "1_1") (pintype "passive"))
      (node (ref "R8") (pin "2") (pinfunction "2_2") (pintype "passive"))
      (node (ref "Y1") (pin "2") (pinfunction "OSC2_2") (pintype "passive"))
    )
    (net (code "118") (name "VCC") (class "Default")
      (node (ref "C1") (pin "1") (pinfunction "1_1") (pintype "passive"))
      (node (ref "C11") (pin "1") (pinfunction "1_1") (pintype "passive"))
      (node (ref "C17") (pin "1") (pinfunction "1_1") (pintype "passive"))
      (node (ref "C19") (pin "1") (pinfunction "1_1") (pintype "passive"))
      (node (ref "C2") (pin "1") (pinfunction "1_1") (pintype "passive"))
      (node (ref "C21") (pin "1") (pinfunction "1_1") (pintype "passive"))
      (node (ref "C23") (pin "1") (pinfunction "1_1") (pintype "passive"))
      (node (ref "C3") (pin "1") (pinfunction "1_1") (pintype "passive"))
      (node (ref "C33") (pin "1") (pinfunction "1_1") (pintype "passive"))
      (node (ref "C4") (pin "1") (pinfunction "1_1") (pintype "passive"))
      (node (ref "C42") (pin "1") (pinfunction "1_1") (pintype "passive"))
      (node (ref "C8") (pin "1") (pinfunction "1_1") (pintype "passive"))
      (node (ref "J14") (pin "2") (pinfunction "2_2") (pintype "passive"))
      (node (ref "R1") (pin "1") (pinfunction "1_1") (pintype "passive"))
      (node (ref "R10") (pin "2") (pinfunction "2_2") (pintype "passive"))
      (node (ref "R112") (pin "2") (pinfunction "2_2") (pintype "passive"))
      (node (ref "R129") (pin "2") (pinfunction "2_2") (pintype "passive"))
      (node (ref "R14") (pin "2") (pinfunction "2_2") (pintype "passive"))
      (node (ref "R15") (pin "2") (pinfunction "2_2") (pintype "passive"))
      (node (ref "R19") (pin "2") (pinfunction "2_2") (pintype "passive"))
      (node (ref "R2") (pin "1") (pinfunction "1_1") (pintype "passive"))
      (node (ref "R21") (pin "2") (pinfunction "2_2") (pintype "passive"))
      (node (ref "R23") (pin "2") (pinfunction "2_2") (pintype "passive"))
      (node (ref "R26") (pin "2") (pinfunction "2_2") (pintype "passive"))
      (node (ref "R27") (pin "2") (pinfunction "2_2") (pintype "passive"))
      (node (ref "R3") (pin "2") (pinfunction "2_2") (pintype "passive"))
      (node (ref "R30") (pin "2") (pinfunction "2_2") (pintype "passive"))
      (node (ref "R4") (pin "2") (pinfunction "2_2") (pintype "passive"))
      (node (ref "R6") (pin "2") (pinfunction "2_2") (pintype "passive"))
      (node (ref "U1") (pin "2") (pinfunction "VCC_2") (pintype "power_in"))
      (node (ref "U13") (pin "5") (pinfunction "VCC_5") (pintype "power_in"))
      (node (ref "U14") (pin "6") (pinfunction "VDD_6") (pintype "power_in"))
      (node (ref "U14") (pin "7") (pinfunction "REGIN_7") (pintype "input"))
      (node (ref "U2") (pin "12") (pinfunction "VDD_12") (pintype "power_in"))
      (node (ref "U2") (pin "25") (pinfunction "AVDD_25") (pintype "power_in"))
      (node (ref "U2") (pin "32") (pinfunction "VDD_32") (pintype "power_in"))
      (node (ref "U2") (pin "48") (pinfunction "VDD_48") (pintype "power_in"))
      (node (ref "U2") (pin "71") (pinfunction "VDD_71") (pintype "power_in"))
      (node (ref "U3") (pin "3") (pinfunction "VCC_3") (pintype "power_in"))
      (node (ref "U4") (pin "2") (pinfunction "VCC_2") (pintype "power_in"))
      (node (ref "U5") (pin "9") (pinfunction "VA_9") (pintype "passive"))
      (node (ref "U7") (pin "3") (pinfunction "OUT_3") (pintype "power_in"))
      (node (ref "U8") (pin "2") (pinfunction "VCC_2") (pintype "power_in"))
      (node (ref "U9") (pin "2") (pinfunction "VCC_2") (pintype "power_in"))
    )
    (net (code "119") (name "unconnected-(D2-NC-Pad1)") (class "Default")
      (node (ref "D2") (pin "1") (pinfunction "NC_1") (pintype "passive"))
    )
    (net (code "120") (name "unconnected-(D7-NC-Pad1)") (class "Default")
      (node (ref "D7") (pin "1") (pinfunction "NC_1") (pintype "passive"))
    )
    (net (code "121") (name "unconnected-(J13-SHLD-Pad5)") (class "Default")
      (node (ref "J13") (pin "5") (pinfunction "SHLD_5") (pintype "passive"))
    )
    (net (code "122") (name "unconnected-(J13-SHLD-Pad6)") (class "Default")
      (node (ref "J13") (pin "6") (pinfunction "SHLD_6") (pintype "passive"))
    )
    (net (code "123") (name "unconnected-(J14-Pad6)") (class "Default")
      (node (ref "J14") (pin "6") (pinfunction "6_6") (pintype "passive"))
    )
    (net (code "124") (name "unconnected-(U2-AN3{slash}CN5{slash}RB3-Pad17)") (class "Default")
      (node (ref "U2") (pin "17") (pinfunction "AN3/CN5/RB3_17") (pintype "bidirectional"))
    )
    (net (code "125") (name "unconnected-(U2-AN4{slash}IC7{slash}CN6{slash}RB4-Pad16)") (class "Default")
      (node (ref "U2") (pin "16") (pinfunction "AN4/IC7/CN6/RB4_16") (pintype "bidirectional"))
    )
    (net (code "126") (name "unconnected-(U2-AN5{slash}IC8{slash}CN7{slash}RB5-Pad15)") (class "Default")
      (node (ref "U2") (pin "15") (pinfunction "AN5/IC8/CN7/RB5_15") (pintype "bidirectional"))
    )
    (net (code "127") (name "unconnected-(U2-AN8{slash}RB8-Pad27)") (class "Default")
      (node (ref "U2") (pin "27") (pinfunction "AN8/RB8_27") (pintype "bidirectional"))
    )
    (net (code "128") (name "unconnected-(U2-AN9{slash}RB9-Pad28)") (class "Default")
      (node (ref "U2") (pin "28") (pinfunction "AN9/RB9_28") (pintype "bidirectional"))
    )
    (net (code "129") (name "unconnected-(U2-AN10{slash}RB10-Pad29)") (class "Default")
      (node (ref "U2") (pin "29") (pinfunction "AN10/RB10_29") (pintype "bidirectional"))
    )
    (net (code "130") (name "unconnected-(U2-AN11{slash}RB11-Pad30)") (class "Default")
      (node (ref "U2") (pin "30") (pinfunction "AN11/RB11_30") (pintype "bidirectional"))
    )
    (net (code "131") (name "unconnected-(U2-AN12{slash}RB12-Pad33)") (class "Default")
      (node (ref "U2") (pin "33") (pinfunction "AN12/RB12_33") (pintype "bidirectional"))
    )
    (net (code "132") (name "unconnected-(U2-EMUC1{slash}SOSCO{slash}T1CK{slash}CN0{slash}RC14-Pad60)") (class "Default")
      (node (ref "U2") (pin "60") (pinfunction "EMUC1/SOSCO/T1CK/CN0/RC14_60") (pintype "bidirectional"))
    )
    (net (code "133") (name "unconnected-(U2-EMUD1{slash}SOSCI{slash}CN1{slash}RC13-Pad59)") (class "Default")
      (node (ref "U2") (pin "59") (pinfunction "EMUD1/SOSCI/CN1/RC13_59") (pintype "bidirectional"))
    )
    (net (code "134") (name "unconnected-(U2-IC1{slash}RD8-Pad54)") (class "Default")
      (node (ref "U2") (pin "54") (pinfunction "IC1/RD8_54") (pintype "bidirectional"))
    )
    (net (code "135") (name "unconnected-(U2-IC2{slash}RD9-Pad55)") (class "Default")
      (node (ref "U2") (pin "55") (pinfunction "IC2/RD9_55") (pintype "bidirectional"))
    )
    (net (code "136") (name "unconnected-(U2-IC3{slash}RD10-Pad56)") (class "Default")
      (node (ref "U2") (pin "56") (pinfunction "IC3/RD10_56") (pintype "bidirectional"))
    )
    (net (code "137") (name "unconnected-(U2-IC4{slash}RD11-Pad57)") (class "Default")
      (node (ref "U2") (pin "57") (pinfunction "IC4/RD11_57") (pintype "bidirectional"))
    )
    (net (code "138") (name "unconnected-(U2-IC5{slash}RD12-Pad64)") (class "Default")
      (node (ref "U2") (pin "64") (pinfunction "IC5/RD12_64") (pintype "bidirectional"))
    )
    (net (code "139") (name "unconnected-(U2-IC6{slash}CN19{slash}RD13-Pad65)") (class "Default")
      (node (ref "U2") (pin "65") (pinfunction "IC6/CN19/RD13_65") (pintype "bidirectional"))
    )
    (net (code "140") (name "unconnected-(U2-IC7{slash}CN20{slash}RD14-Pad37)") (class "Default")
      (node (ref "U2") (pin "37") (pinfunction "IC7/CN20/RD14_37") (pintype "bidirectional"))
    )
    (net (code "141") (name "unconnected-(U2-IC8{slash}CN21{slash}RD15-Pad38)") (class "Default")
      (node (ref "U2") (pin "38") (pinfunction "IC8/CN21/RD15_38") (pintype "bidirectional"))
    )
    (net (code "142") (name "unconnected-(U2-OC3{slash}RD2-Pad62)") (class "Default")
      (node (ref "U2") (pin "62") (pinfunction "OC3/RD2_62") (pintype "bidirectional"))
    )
    (net (code "143") (name "unconnected-(U2-OC4{slash}RD3-Pad63)") (class "Default")
      (node (ref "U2") (pin "63") (pinfunction "OC4/RD3_63") (pintype "bidirectional"))
    )
    (net (code "144") (name "unconnected-(U2-OC5{slash}CN13{slash}RD4-Pad66)") (class "Default")
      (node (ref "U2") (pin "66") (pinfunction "OC5/CN13/RD4_66") (pintype "bidirectional"))
    )
    (net (code "145") (name "unconnected-(U2-OC6{slash}CN14{slash}RD5-Pad67)") (class "Default")
      (node (ref "U2") (pin "67") (pinfunction "OC6/CN14/RD5_67") (pintype "bidirectional"))
    )
    (net (code "146") (name "unconnected-(U2-OC7{slash}CN15{slash}RD6-Pad68)") (class "Default")
      (node (ref "U2") (pin "68") (pinfunction "OC7/CN15/RD6_68") (pintype "bidirectional"))
    )
    (net (code "147") (name "unconnected-(U2-PGC{slash}EMUC{slash}AN6{slash}OCFA{slash}RB6-Pad21)") (class "Default")
      (node (ref "U2") (pin "21") (pinfunction "PGC/EMUC/AN6/OCFA/RB6_21") (pintype "bidirectional"))
    )
    (net (code "148") (name "unconnected-(U2-PGD{slash}EMUD{slash}AN7{slash}RB7-Pad22)") (class "Default")
      (node (ref "U2") (pin "22") (pinfunction "PGD/EMUD/AN7/RB7_22") (pintype "bidirectional"))
    )
    (net (code "149") (name "unconnected-(U2-SCK2{slash}CN8{slash}RG6-Pad6)") (class "Default")
      (node (ref "U2") (pin "6") (pinfunction "SCK2/CN8/RG6_6") (pintype "bidirectional"))
    )
    (net (code "150") (name "unconnected-(U2-SCL{slash}RG2-Pad47)") (class "Default")
      (node (ref "U2") (pin "47") (pinfunction "SCL/RG2_47") (pintype "bidirectional"))
    )
    (net (code "151") (name "unconnected-(U2-SDI2{slash}CN9{slash}RG7-Pad7)") (class "Default")
      (node (ref "U2") (pin "7") (pinfunction "SDI2/CN9/RG7_7") (pintype "bidirectional"))
    )
    (net (code "152") (name "unconnected-(U2-SDO2{slash}CN10{slash}RG8-Pad8)") (class "Default")
      (node (ref "U2") (pin "8") (pinfunction "SDO2/CN10/RG8_8") (pintype "bidirectional"))
    )
    (net (code "153") (name "unconnected-(U2-T2CK{slash}RC1-Pad2)") (class "Default")
      (node (ref "U2") (pin "2") (pinfunction "T2CK/RC1_2") (pintype "bidirectional"))
    )
    (net (code "154") (name "unconnected-(U2-T3CK{slash}RC2-Pad3)") (class "Default")
      (node (ref "U2") (pin "3") (pinfunction "T3CK/RC2_3") (pintype "bidirectional"))
    )
    (net (code "155") (name "unconnected-(U2-U1RX{slash}RF2-Pad42)") (class "Default")
      (node (ref "U2") (pin "42") (pinfunction "U1RX/RF2_42") (pintype "bidirectional"))
    )
    (net (code "156") (name "unconnected-(U2-U1TX{slash}RF3-Pad41)") (class "Default")
      (node (ref "U2") (pin "41") (pinfunction "U1TX/RF3_41") (pintype "bidirectional"))
    )
    (net (code "157") (name "unconnected-(U2-~{SS2}{slash}CN11{slash}RG9-Pad10)") (class "Default")
      (node (ref "U2") (pin "10") (pinfunction "~{SS2}/CN11/RG9_10") (pintype "bidirectional"))
    )
    (net (code "158") (name "unconnected-(U3-VREF-Pad5)") (class "Default")
      (node (ref "U3") (pin "5") (pinfunction "VREF_5") (pintype "passive"))
    )
    (net (code "159") (name "unconnected-(U5-AOUTL-Pad7)") (class "Default")
      (node (ref "U5") (pin "7") (pinfunction "AOUTL_7") (pintype "passive"))
    )
    (net (code "160") (name "unconnected-(U6-NC-Pad5)") (class "Default")
      (node (ref "U6") (pin "5") (pinfunction "NC_5") (pintype "passive"))
    )
    (net (code "161") (name "unconnected-(U11-NC-Pad5)") (class "Default")
      (node (ref "U11") (pin "5") (pinfunction "NC_5") (pintype "passive"))
    )
    (net (code "162") (name "unconnected-(U12-Pad5)") (class "Default")
      (node (ref "U12") (pin "5") (pinfunction "5_5") (pintype "passive"))
    )
    (net (code "163") (name "unconnected-(U12-Pad6)") (class "Default")
      (node (ref "U12") (pin "6") (pinfunction "6_6") (pintype "passive"))
    )
    (net (code "164") (name "unconnected-(U14-CTS-Pad23)") (class "Default")
      (node (ref "U14") (pin "23") (pinfunction "CTS_23") (pintype "input"))
    )
    (net (code "165") (name "unconnected-(U14-DCD-Pad1)") (class "Default")
      (node (ref "U14") (pin "1") (pinfunction "DCD_1") (pintype "input"))
    )
    (net (code "166") (name "unconnected-(U14-DSR-Pad27)") (class "Default")
      (node (ref "U14") (pin "27") (pinfunction "DSR_27") (pintype "input"))
    )
    (net (code "167") (name "unconnected-(U14-DTR-Pad28)") (class "Default")
      (node (ref "U14") (pin "28") (pinfunction "DTR_28") (pintype "output"))
    )
    (net (code "168") (name "unconnected-(U14-RI-Pad2)") (class "Default")
      (node (ref "U14") (pin "2") (pinfunction "RI_2") (pintype "input"))
    )
    (net (code "169") (name "unconnected-(U14-RTS-Pad24)") (class "Default")
      (node (ref "U14") (pin "24") (pinfunction "RTS_24") (pintype "output"))
    )
    (net (code "170") (name "unconnected-(U14-SUSPEND-Pad12)") (class "Default")
      (node (ref "U14") (pin "12") (pinfunction "SUSPEND_12") (pintype "output"))
    )
    (net (code "171") (name "unconnected-(U14-~{SUSPEND}-Pad11)") (class "Default")
      (node (ref "U14") (pin "11") (pinfunction "~{SUSPEND}_11") (pintype "output"))
    )
  )
)
